# multishift.net
KiCad netlist of a schematic drawn in EAGLE
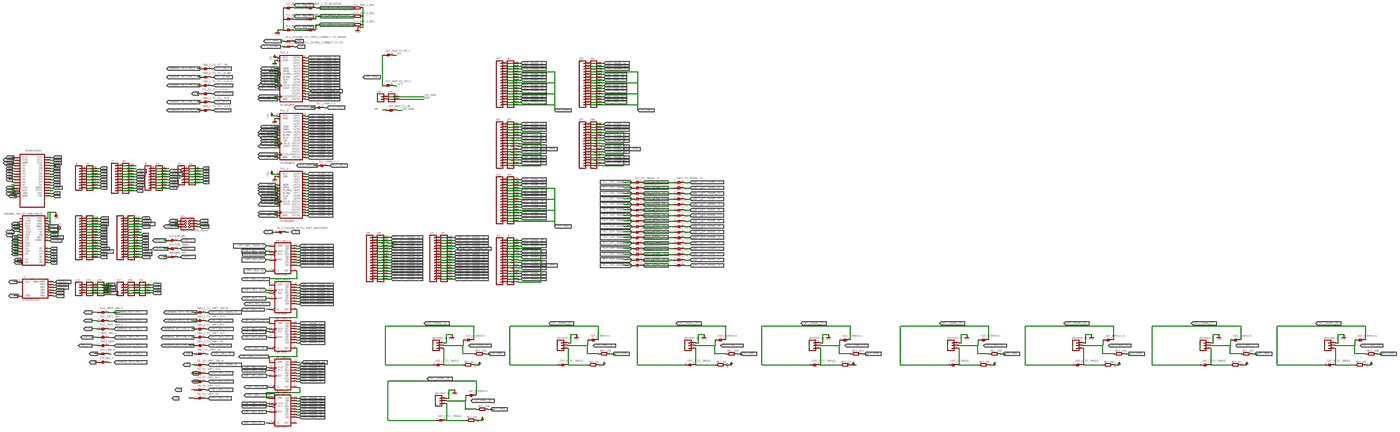
[diagram p0: schematic, sheet 1, overview]
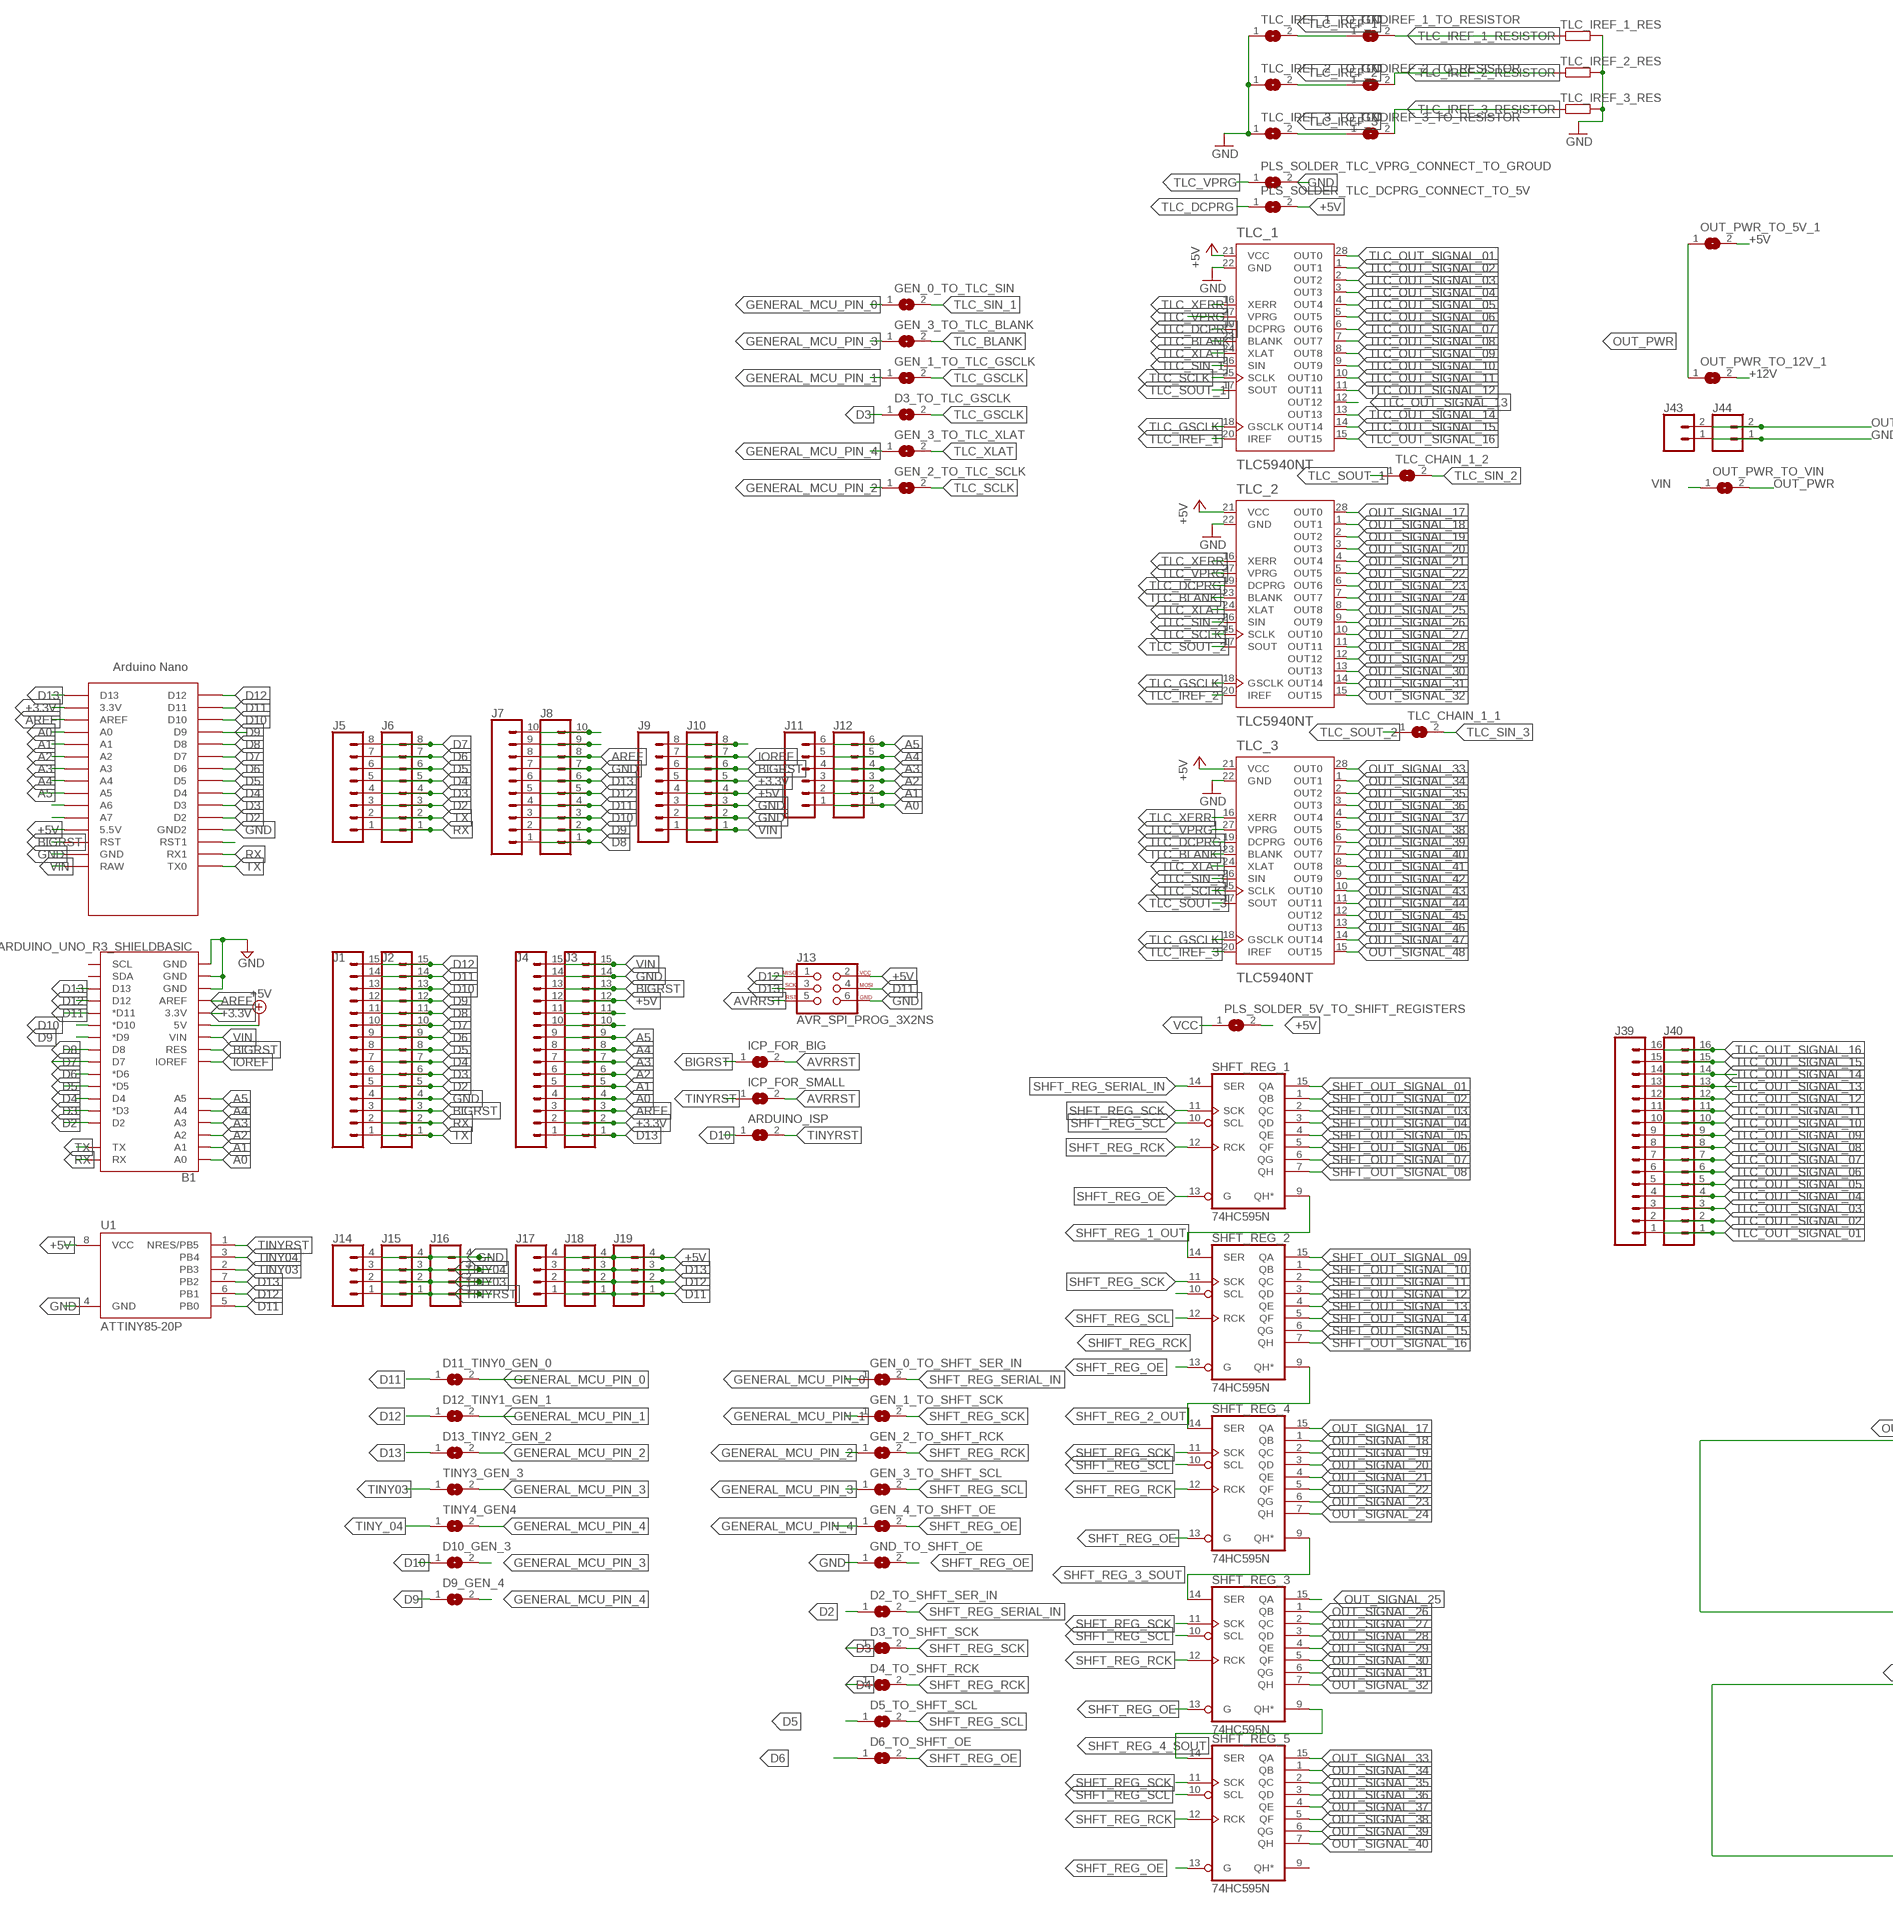
[diagram p1: schematic, sheet 1, part 1 of 4]
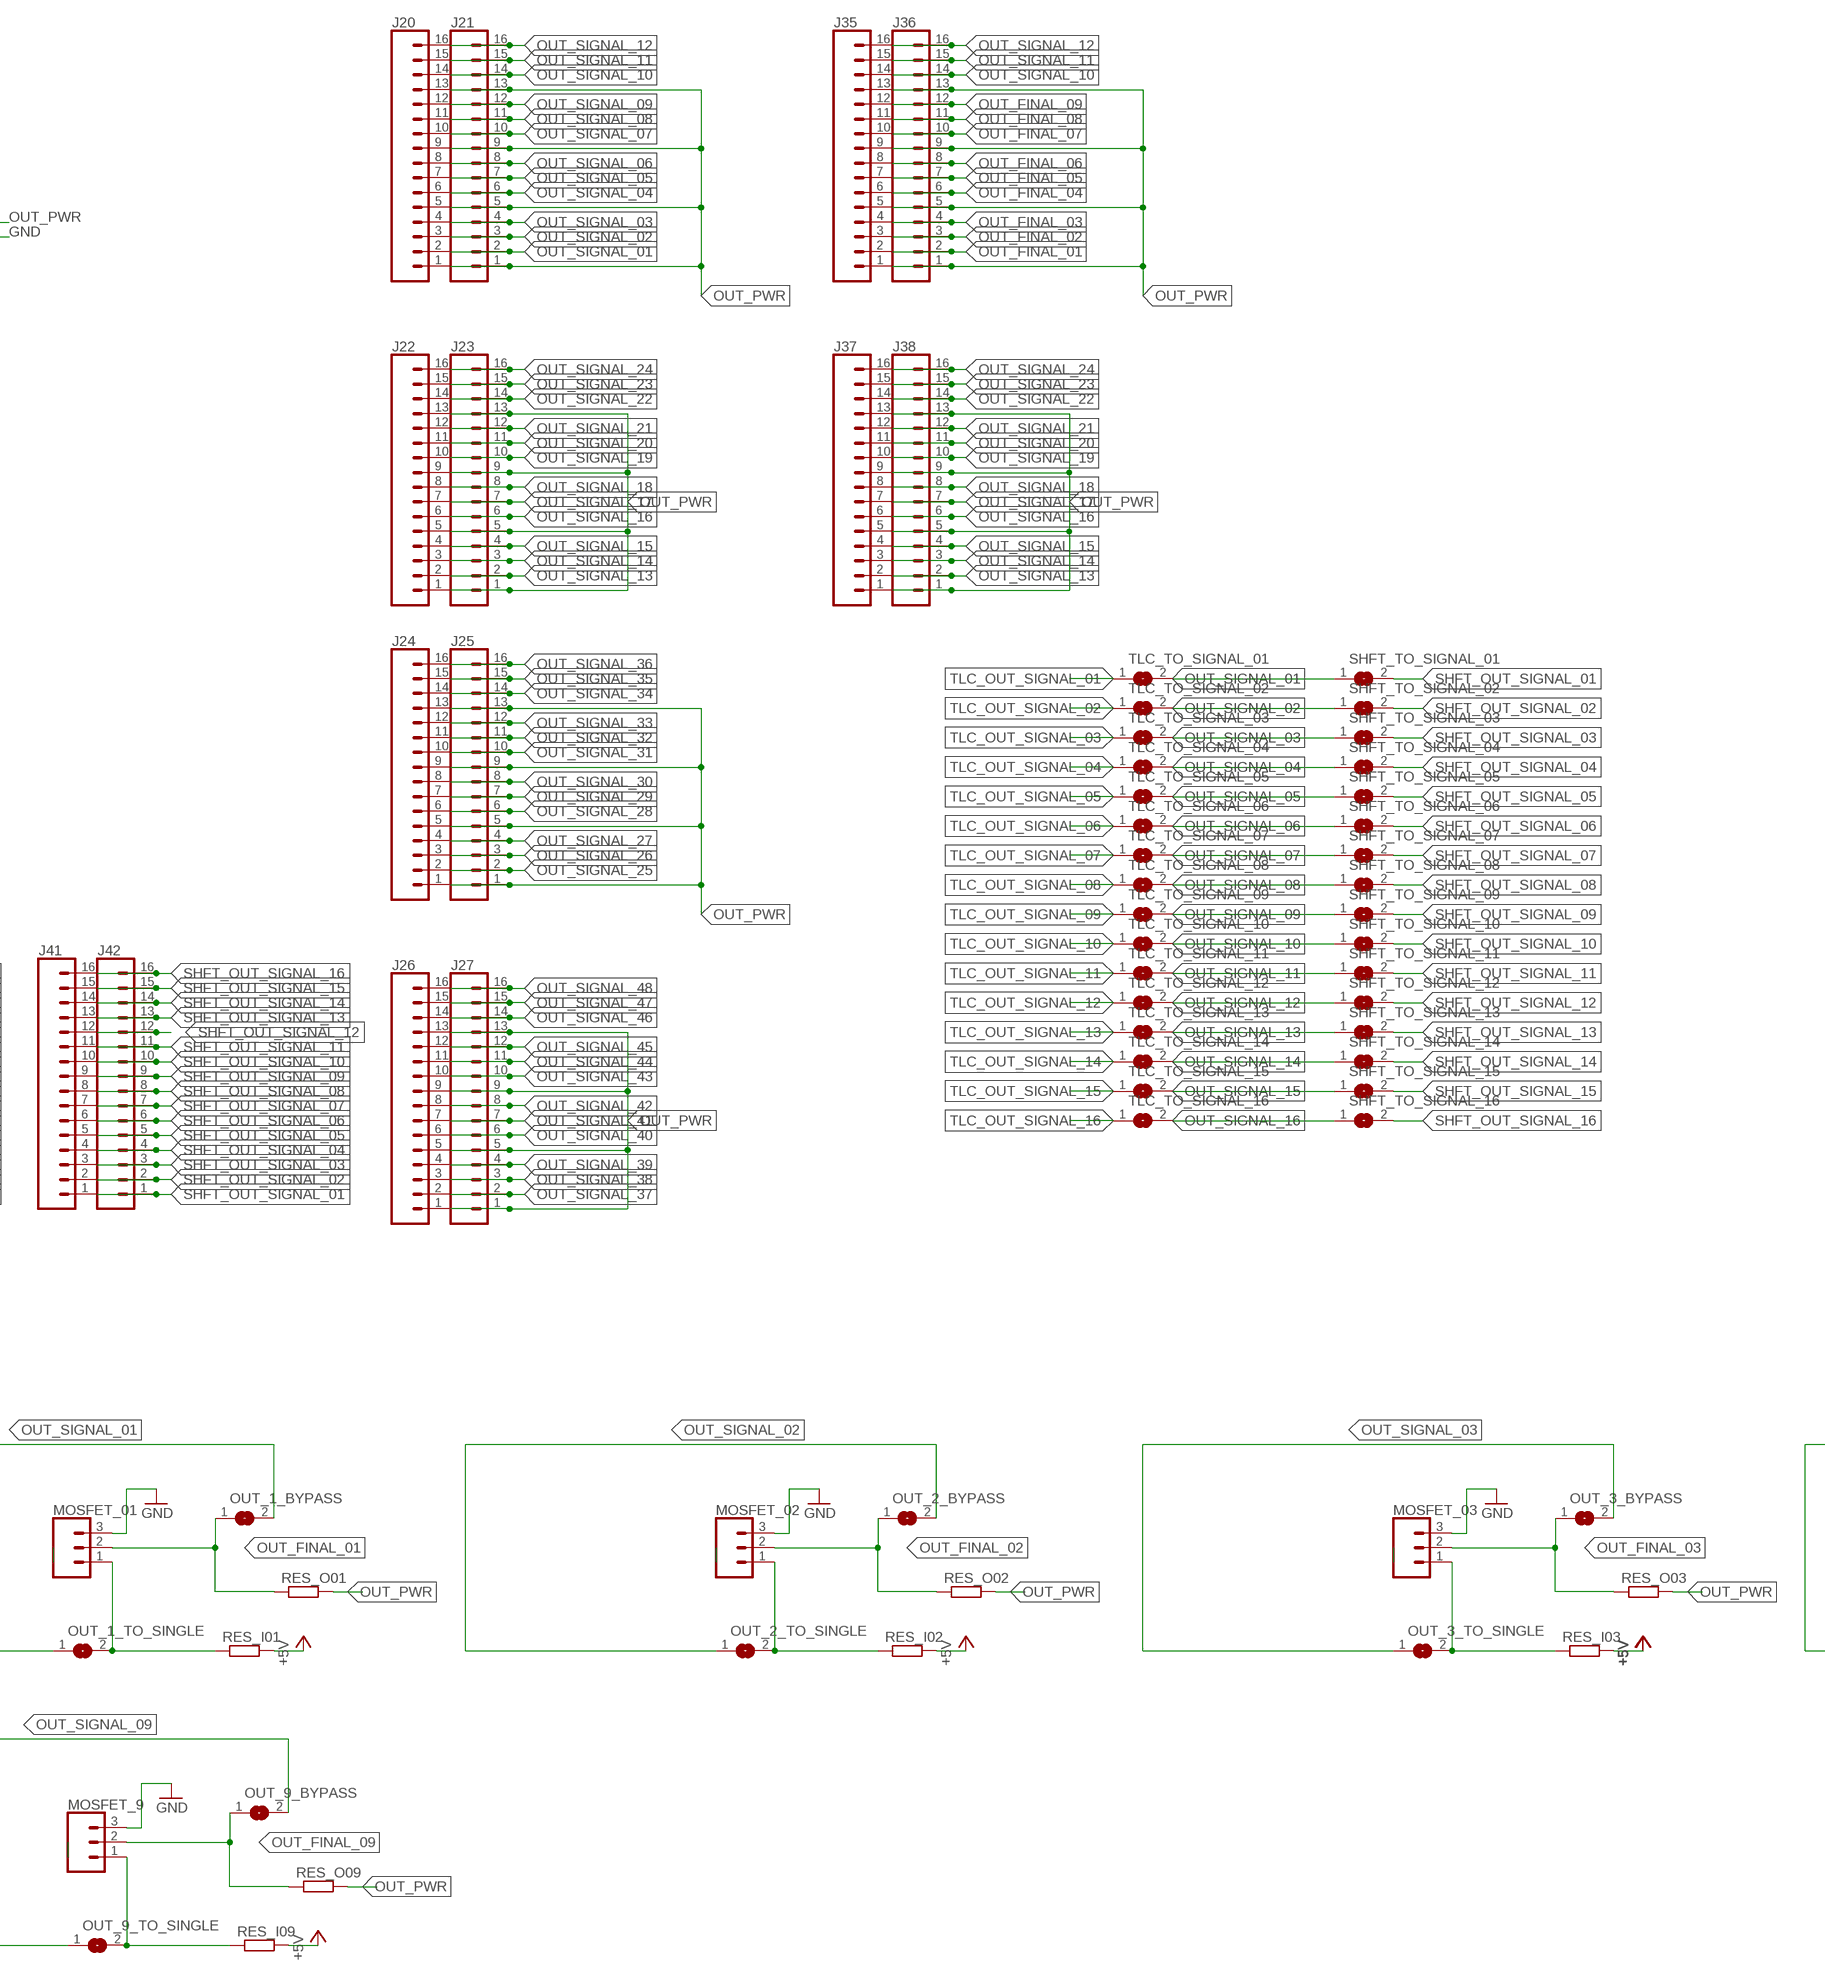
[diagram p2: schematic, sheet 1, part 2 of 4]
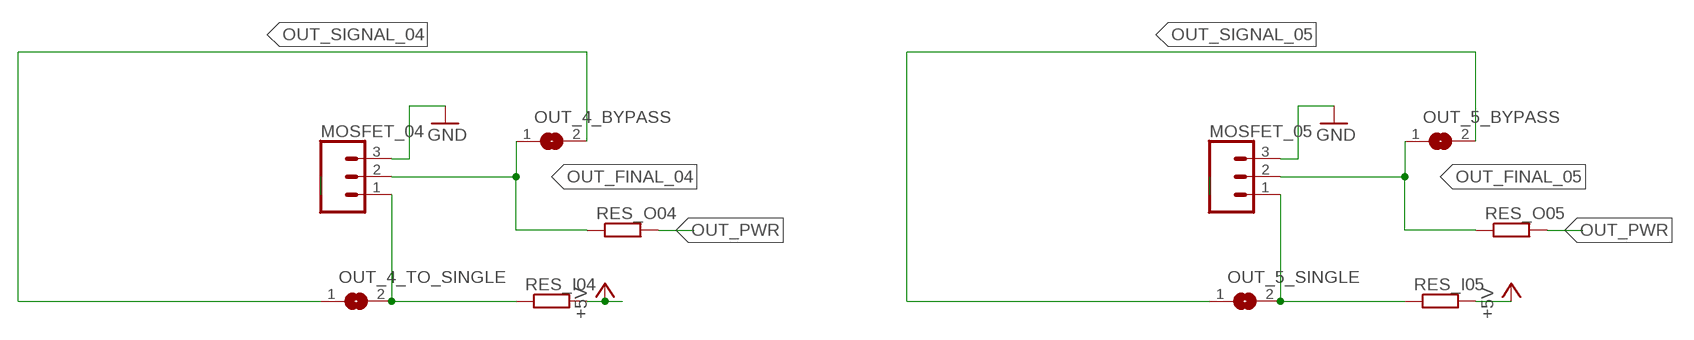
[diagram p3: schematic, sheet 1, part 3 of 4]
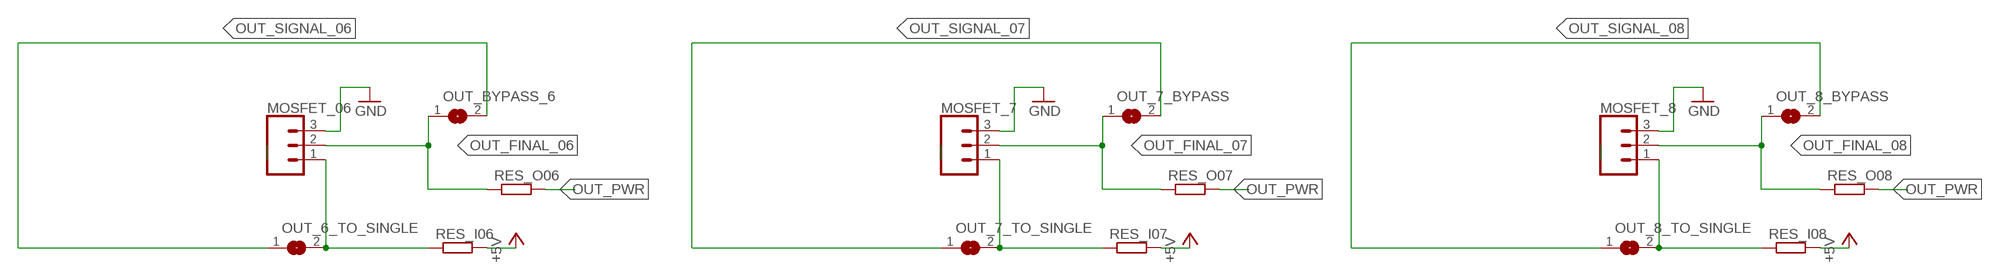
[diagram p4: schematic, sheet 1, part 4 of 4]

(export (version "E")
  (design (tool "Eeschema 10.0.6"))
  (components
    (comp (ref "ARDUINO_ISP")
      (value "SJ")
      (footprint "eagle-import:SJ")
      (libsource (lib "eagle-import") (part "SJ"))
    )
    (comp (ref "B1")
      (value "ARDUINO_UNO_R3_SHIELDBASIC")
      (footprint "eagle-import:UNO_R3_SHIELD")
      (libsource (lib "eagle-import") (part "ARDUINO_UNO_R3_SHIELDBASIC"))
    )
    (comp (ref "D2_TO_SHFT_SER_IN")
      (value "SJ")
      (footprint "eagle-import:SJ")
      (libsource (lib "eagle-import") (part "SJ"))
    )
    (comp (ref "D3_TO_SHFT_SCK")
      (value "SJ")
      (footprint "eagle-import:SJ")
      (libsource (lib "eagle-import") (part "SJ"))
    )
    (comp (ref "D3_TO_TLC_GSCLK")
      (value "SJ")
      (footprint "eagle-import:SJ")
      (libsource (lib "eagle-import") (part "SJ"))
    )
    (comp (ref "D4_TO_SHFT_RCK")
      (value "SJ")
      (footprint "eagle-import:SJ")
      (libsource (lib "eagle-import") (part "SJ"))
    )
    (comp (ref "D5_TO_SHFT_SCL")
      (value "SJ")
      (footprint "eagle-import:SJ")
      (libsource (lib "eagle-import") (part "SJ"))
    )
    (comp (ref "D6_TO_SHFT_OE")
      (value "SJ")
      (footprint "eagle-import:SJ")
      (libsource (lib "eagle-import") (part "SJ"))
    )
    (comp (ref "D9_GEN_4")
      (value "SJ")
      (footprint "eagle-import:SJ")
      (libsource (lib "eagle-import") (part "SJ"))
    )
    (comp (ref "D10_GEN_3")
      (value "SJ")
      (footprint "eagle-import:SJ")
      (libsource (lib "eagle-import") (part "SJ"))
    )
    (comp (ref "D11_TINY0_GEN_0")
      (value "SJ")
      (footprint "eagle-import:SJ")
      (libsource (lib "eagle-import") (part "SJ"))
    )
    (comp (ref "D12_TINY1_GEN_1")
      (value "SJ")
      (footprint "eagle-import:SJ")
      (libsource (lib "eagle-import") (part "SJ"))
    )
    (comp (ref "D13_TINY2_GEN_2")
      (value "SJ")
      (footprint "eagle-import:SJ")
      (libsource (lib "eagle-import") (part "SJ"))
    )
    (comp (ref "GEN_0_TO_SHFT_SER_IN")
      (value "SJ")
      (footprint "eagle-import:SJ")
      (libsource (lib "eagle-import") (part "SJ"))
    )
    (comp (ref "GEN_0_TO_TLC_SIN")
      (value "SJ")
      (footprint "eagle-import:SJ")
      (libsource (lib "eagle-import") (part "SJ"))
    )
    (comp (ref "GEN_1_TO_SHFT_SCK")
      (value "SJ")
      (footprint "eagle-import:SJ")
      (libsource (lib "eagle-import") (part "SJ"))
    )
    (comp (ref "GEN_1_TO_TLC_GSCLK")
      (value "SJ")
      (footprint "eagle-import:SJ")
      (libsource (lib "eagle-import") (part "SJ"))
    )
    (comp (ref "GEN_2_TO_SHFT_RCK")
      (value "SJ")
      (footprint "eagle-import:SJ")
      (libsource (lib "eagle-import") (part "SJ"))
    )
    (comp (ref "GEN_2_TO_TLC_SCLK")
      (value "SJ")
      (footprint "eagle-import:SJ")
      (libsource (lib "eagle-import") (part "SJ"))
    )
    (comp (ref "GEN_3_TO_SHFT_SCL")
      (value "SJ")
      (footprint "eagle-import:SJ")
      (libsource (lib "eagle-import") (part "SJ"))
    )
    (comp (ref "GEN_3_TO_TLC_BLANK")
      (value "SJ")
      (footprint "eagle-import:SJ")
      (libsource (lib "eagle-import") (part "SJ"))
    )
    (comp (ref "GEN_3_TO_TLC_XLAT")
      (value "SJ")
      (footprint "eagle-import:SJ")
      (libsource (lib "eagle-import") (part "SJ"))
    )
    (comp (ref "GEN_4_TO_SHFT_OE")
      (value "SJ")
      (footprint "eagle-import:SJ")
      (libsource (lib "eagle-import") (part "SJ"))
    )
    (comp (ref "GND_TO_SHFT_OE")
      (value "SJ")
      (footprint "eagle-import:SJ")
      (libsource (lib "eagle-import") (part "SJ"))
    )
    (comp (ref "ICP_FOR_BIG")
      (value "SJ")
      (footprint "eagle-import:SJ")
      (libsource (lib "eagle-import") (part "SJ"))
    )
    (comp (ref "ICP_FOR_SMALL")
      (value "SJ")
      (footprint "eagle-import:SJ")
      (libsource (lib "eagle-import") (part "SJ"))
    )
    (comp (ref "J1")
      (value "CONN_15")
      (footprint "eagle-import:1X15")
      (libsource (lib "eagle-import") (part "CONN_15"))
    )
    (comp (ref "J2")
      (value "CONN_15")
      (footprint "eagle-import:1X15")
      (libsource (lib "eagle-import") (part "CONN_15"))
    )
    (comp (ref "J3")
      (value "CONN_15")
      (footprint "eagle-import:1X15")
      (libsource (lib "eagle-import") (part "CONN_15"))
    )
    (comp (ref "J4")
      (value "CONN_15")
      (footprint "eagle-import:1X15")
      (libsource (lib "eagle-import") (part "CONN_15"))
    )
    (comp (ref "J5")
      (value "CONN_08\"")
      (footprint "eagle-import:1X08")
      (libsource (lib "eagle-import") (part "CONN_08{dblquote}"))
    )
    (comp (ref "J6")
      (value "CONN_08\"")
      (footprint "eagle-import:1X08")
      (libsource (lib "eagle-import") (part "CONN_08{dblquote}"))
    )
    (comp (ref "J7")
      (value "CONN_10\"")
      (footprint "eagle-import:1X10")
      (libsource (lib "eagle-import") (part "CONN_10{dblquote}"))
    )
    (comp (ref "J8")
      (value "CONN_10\"")
      (footprint "eagle-import:1X10")
      (libsource (lib "eagle-import") (part "CONN_10{dblquote}"))
    )
    (comp (ref "J9")
      (value "CONN_08\"")
      (footprint "eagle-import:1X08")
      (libsource (lib "eagle-import") (part "CONN_08{dblquote}"))
    )
    (comp (ref "J10")
      (value "CONN_08\"")
      (footprint "eagle-import:1X08")
      (libsource (lib "eagle-import") (part "CONN_08{dblquote}"))
    )
    (comp (ref "J11")
      (value "CONN_06SILK_FEMALE_PTH")
      (footprint "eagle-import:1X06")
      (libsource (lib "eagle-import") (part "CONN_06SILK_FEMALE_PTH"))
    )
    (comp (ref "J12")
      (value "CONN_06SILK_FEMALE_PTH")
      (footprint "eagle-import:1X06")
      (libsource (lib "eagle-import") (part "CONN_06SILK_FEMALE_PTH"))
    )
    (comp (ref "J13")
      (value "AVR_SPI_PROG_3X2NS")
      (footprint "eagle-import:2X3-NS")
      (libsource (lib "eagle-import") (part "AVR_SPI_PROG_3X2NS"))
    )
    (comp (ref "J14")
      (value "CONN_04")
      (footprint "eagle-import:1X04")
      (libsource (lib "eagle-import") (part "CONN_04"))
    )
    (comp (ref "J15")
      (value "CONN_04")
      (footprint "eagle-import:1X04")
      (libsource (lib "eagle-import") (part "CONN_04"))
    )
    (comp (ref "J16")
      (value "CONN_04")
      (footprint "eagle-import:1X04")
      (libsource (lib "eagle-import") (part "CONN_04"))
    )
    (comp (ref "J17")
      (value "CONN_04")
      (footprint "eagle-import:1X04")
      (libsource (lib "eagle-import") (part "CONN_04"))
    )
    (comp (ref "J18")
      (value "CONN_04")
      (footprint "eagle-import:1X04")
      (libsource (lib "eagle-import") (part "CONN_04"))
    )
    (comp (ref "J19")
      (value "CONN_04")
      (footprint "eagle-import:1X04")
      (libsource (lib "eagle-import") (part "CONN_04"))
    )
    (comp (ref "J20")
      (value "CONN_16")
      (footprint "eagle-import:1X16")
      (libsource (lib "eagle-import") (part "CONN_16"))
    )
    (comp (ref "J21")
      (value "CONN_16")
      (footprint "eagle-import:1X16")
      (libsource (lib "eagle-import") (part "CONN_16"))
    )
    (comp (ref "J22")
      (value "CONN_16")
      (footprint "eagle-import:1X16")
      (libsource (lib "eagle-import") (part "CONN_16"))
    )
    (comp (ref "J23")
      (value "CONN_16")
      (footprint "eagle-import:1X16")
      (libsource (lib "eagle-import") (part "CONN_16"))
    )
    (comp (ref "J24")
      (value "CONN_16")
      (footprint "eagle-import:1X16")
      (libsource (lib "eagle-import") (part "CONN_16"))
    )
    (comp (ref "J25")
      (value "CONN_16")
      (footprint "eagle-import:1X16")
      (libsource (lib "eagle-import") (part "CONN_16"))
    )
    (comp (ref "J26")
      (value "CONN_16")
      (footprint "eagle-import:1X16")
      (libsource (lib "eagle-import") (part "CONN_16"))
    )
    (comp (ref "J27")
      (value "CONN_16")
      (footprint "eagle-import:1X16")
      (libsource (lib "eagle-import") (part "CONN_16"))
    )
    (comp (ref "J35")
      (value "CONN_16")
      (footprint "eagle-import:1X16")
      (libsource (lib "eagle-import") (part "CONN_16"))
    )
    (comp (ref "J36")
      (value "CONN_16")
      (footprint "eagle-import:1X16")
      (libsource (lib "eagle-import") (part "CONN_16"))
    )
    (comp (ref "J37")
      (value "CONN_16")
      (footprint "eagle-import:1X16")
      (libsource (lib "eagle-import") (part "CONN_16"))
    )
    (comp (ref "J38")
      (value "CONN_16")
      (footprint "eagle-import:1X16")
      (libsource (lib "eagle-import") (part "CONN_16"))
    )
    (comp (ref "J39")
      (value "CONN_16")
      (footprint "eagle-import:1X16")
      (libsource (lib "eagle-import") (part "CONN_16"))
    )
    (comp (ref "J40")
      (value "CONN_16")
      (footprint "eagle-import:1X16")
      (libsource (lib "eagle-import") (part "CONN_16"))
    )
    (comp (ref "J41")
      (value "CONN_16")
      (footprint "eagle-import:1X16")
      (libsource (lib "eagle-import") (part "CONN_16"))
    )
    (comp (ref "J42")
      (value "CONN_16")
      (footprint "eagle-import:1X16")
      (libsource (lib "eagle-import") (part "CONN_16"))
    )
    (comp (ref "J43")
      (value "CONN_025MM")
      (footprint "eagle-import:SCREWTERMINAL-5MM-2")
      (libsource (lib "eagle-import") (part "CONN_025MM"))
    )
    (comp (ref "J44")
      (value "CONN_025MM")
      (footprint "eagle-import:SCREWTERMINAL-5MM-2")
      (libsource (lib "eagle-import") (part "CONN_025MM"))
    )
    (comp (ref "MOSFET_01")
      (value "CONN_03")
      (footprint "eagle-import:1X03")
      (libsource (lib "eagle-import") (part "CONN_03"))
    )
    (comp (ref "MOSFET_02")
      (value "CONN_03")
      (footprint "eagle-import:1X03")
      (libsource (lib "eagle-import") (part "CONN_03"))
    )
    (comp (ref "MOSFET_03")
      (value "CONN_03")
      (footprint "eagle-import:1X03")
      (libsource (lib "eagle-import") (part "CONN_03"))
    )
    (comp (ref "MOSFET_04")
      (value "CONN_03")
      (footprint "eagle-import:1X03")
      (libsource (lib "eagle-import") (part "CONN_03"))
    )
    (comp (ref "MOSFET_05")
      (value "CONN_03")
      (footprint "eagle-import:1X03")
      (libsource (lib "eagle-import") (part "CONN_03"))
    )
    (comp (ref "MOSFET_06")
      (value "CONN_03")
      (footprint "eagle-import:1X03")
      (libsource (lib "eagle-import") (part "CONN_03"))
    )
    (comp (ref "MOSFET_7")
      (value "CONN_03")
      (footprint "eagle-import:1X03")
      (libsource (lib "eagle-import") (part "CONN_03"))
    )
    (comp (ref "MOSFET_8")
      (value "CONN_03")
      (footprint "eagle-import:1X03")
      (libsource (lib "eagle-import") (part "CONN_03"))
    )
    (comp (ref "MOSFET_9")
      (value "CONN_03")
      (footprint "eagle-import:1X03")
      (libsource (lib "eagle-import") (part "CONN_03"))
    )
    (comp (ref "OUT_1_BYPASS")
      (value "SJ")
      (footprint "eagle-import:SJ")
      (libsource (lib "eagle-import") (part "SJ"))
    )
    (comp (ref "OUT_1_TO_SINGLE")
      (value "SJ")
      (footprint "eagle-import:SJ")
      (libsource (lib "eagle-import") (part "SJ"))
    )
    (comp (ref "OUT_2_BYPASS")
      (value "SJ")
      (footprint "eagle-import:SJ")
      (libsource (lib "eagle-import") (part "SJ"))
    )
    (comp (ref "OUT_2_TO_SINGLE")
      (value "SJ")
      (footprint "eagle-import:SJ")
      (libsource (lib "eagle-import") (part "SJ"))
    )
    (comp (ref "OUT_3_BYPASS")
      (value "SJ")
      (footprint "eagle-import:SJ")
      (libsource (lib "eagle-import") (part "SJ"))
    )
    (comp (ref "OUT_3_TO_SINGLE")
      (value "SJ")
      (footprint "eagle-import:SJ")
      (libsource (lib "eagle-import") (part "SJ"))
    )
    (comp (ref "OUT_4_BYPASS")
      (value "SJ")
      (footprint "eagle-import:SJ")
      (libsource (lib "eagle-import") (part "SJ"))
    )
    (comp (ref "OUT_4_TO_SINGLE")
      (value "SJ")
      (footprint "eagle-import:SJ")
      (libsource (lib "eagle-import") (part "SJ"))
    )
    (comp (ref "OUT_5_BYPASS")
      (value "SJ")
      (footprint "eagle-import:SJ")
      (libsource (lib "eagle-import") (part "SJ"))
    )
    (comp (ref "OUT_5_SINGLE")
      (value "SJ")
      (footprint "eagle-import:SJ")
      (libsource (lib "eagle-import") (part "SJ"))
    )
    (comp (ref "OUT_6_TO_SINGLE")
      (value "SJ")
      (footprint "eagle-import:SJ")
      (libsource (lib "eagle-import") (part "SJ"))
    )
    (comp (ref "OUT_7_BYPASS")
      (value "SJ")
      (footprint "eagle-import:SJ")
      (libsource (lib "eagle-import") (part "SJ"))
    )
    (comp (ref "OUT_7_TO_SINGLE")
      (value "SJ")
      (footprint "eagle-import:SJ")
      (libsource (lib "eagle-import") (part "SJ"))
    )
    (comp (ref "OUT_8_BYPASS")
      (value "SJ")
      (footprint "eagle-import:SJ")
      (libsource (lib "eagle-import") (part "SJ"))
    )
    (comp (ref "OUT_8_TO_SINGLE")
      (value "SJ")
      (footprint "eagle-import:SJ")
      (libsource (lib "eagle-import") (part "SJ"))
    )
    (comp (ref "OUT_9_BYPASS")
      (value "SJ")
      (footprint "eagle-import:SJ")
      (libsource (lib "eagle-import") (part "SJ"))
    )
    (comp (ref "OUT_9_TO_SINGLE")
      (value "SJ")
      (footprint "eagle-import:SJ")
      (libsource (lib "eagle-import") (part "SJ"))
    )
    (comp (ref "OUT_BYPASS_6")
      (value "SJ")
      (footprint "eagle-import:SJ")
      (libsource (lib "eagle-import") (part "SJ"))
    )
    (comp (ref "OUT_PWR_TO_5V_1")
      (value "SJ")
      (footprint "eagle-import:SJ")
      (libsource (lib "eagle-import") (part "SJ"))
    )
    (comp (ref "OUT_PWR_TO_12V_1")
      (value "SJ")
      (footprint "eagle-import:SJ")
      (libsource (lib "eagle-import") (part "SJ"))
    )
    (comp (ref "OUT_PWR_TO_VIN")
      (value "SJ")
      (footprint "eagle-import:SJ")
      (libsource (lib "eagle-import") (part "SJ"))
    )
    (comp (ref "PLS_SOLDER_5V_TO_SHIFT_REGISTERS")
      (value "SJ")
      (footprint "eagle-import:SJ")
      (libsource (lib "eagle-import") (part "SJ"))
    )
    (comp (ref "PLS_SOLDER_TLC_DCPRG_CONNECT_TO_5V")
      (value "SJ")
      (footprint "eagle-import:SJ")
      (libsource (lib "eagle-import") (part "SJ"))
    )
    (comp (ref "PLS_SOLDER_TLC_VPRG_CONNECT_TO_GROUD")
      (value "SJ")
      (footprint "eagle-import:SJ")
      (libsource (lib "eagle-import") (part "SJ"))
    )
    (comp (ref "RES_I01")
      (value "R-EU_0204/7")
      (footprint "eagle-import:0204_7")
      (libsource (lib "eagle-import") (part "R-EU_0204/7"))
    )
    (comp (ref "RES_I02")
      (value "R-EU_0204/7")
      (footprint "eagle-import:0204_7")
      (libsource (lib "eagle-import") (part "R-EU_0204/7"))
    )
    (comp (ref "RES_I03")
      (value "R-EU_0204/7")
      (footprint "eagle-import:0204_7")
      (libsource (lib "eagle-import") (part "R-EU_0204/7"))
    )
    (comp (ref "RES_I04")
      (value "R-EU_0204/7")
      (footprint "eagle-import:0204_7")
      (libsource (lib "eagle-import") (part "R-EU_0204/7"))
    )
    (comp (ref "RES_I05")
      (value "R-EU_0204/7")
      (footprint "eagle-import:0204_7")
      (libsource (lib "eagle-import") (part "R-EU_0204/7"))
    )
    (comp (ref "RES_I06")
      (value "R-EU_0204/7")
      (footprint "eagle-import:0204_7")
      (libsource (lib "eagle-import") (part "R-EU_0204/7"))
    )
    (comp (ref "RES_I07")
      (value "R-EU_0204/7")
      (footprint "eagle-import:0204_7")
      (libsource (lib "eagle-import") (part "R-EU_0204/7"))
    )
    (comp (ref "RES_I08")
      (value "R-EU_0204/7")
      (footprint "eagle-import:0204_7")
      (libsource (lib "eagle-import") (part "R-EU_0204/7"))
    )
    (comp (ref "RES_I09")
      (value "R-EU_0204/7")
      (footprint "eagle-import:0204_7")
      (libsource (lib "eagle-import") (part "R-EU_0204/7"))
    )
    (comp (ref "RES_O01")
      (value "R-EU_0204/7")
      (footprint "eagle-import:0204_7")
      (libsource (lib "eagle-import") (part "R-EU_0204/7"))
    )
    (comp (ref "RES_O02")
      (value "R-EU_0204/7")
      (footprint "eagle-import:0204_7")
      (libsource (lib "eagle-import") (part "R-EU_0204/7"))
    )
    (comp (ref "RES_O03")
      (value "R-EU_0204/7")
      (footprint "eagle-import:0204_7")
      (libsource (lib "eagle-import") (part "R-EU_0204/7"))
    )
    (comp (ref "RES_O04")
      (value "R-EU_0204/7")
      (footprint "eagle-import:0204_7")
      (libsource (lib "eagle-import") (part "R-EU_0204/7"))
    )
    (comp (ref "RES_O05")
      (value "R-EU_0204/7")
      (footprint "eagle-import:0204_7")
      (libsource (lib "eagle-import") (part "R-EU_0204/7"))
    )
    (comp (ref "RES_O06")
      (value "R-EU_0204/7")
      (footprint "eagle-import:0204_7")
      (libsource (lib "eagle-import") (part "R-EU_0204/7"))
    )
    (comp (ref "RES_O07")
      (value "R-EU_0204/7")
      (footprint "eagle-import:0204_7")
      (libsource (lib "eagle-import") (part "R-EU_0204/7"))
    )
    (comp (ref "RES_O08")
      (value "R-EU_0204/7")
      (footprint "eagle-import:0204_7")
      (libsource (lib "eagle-import") (part "R-EU_0204/7"))
    )
    (comp (ref "RES_O09")
      (value "R-EU_0204/7")
      (footprint "eagle-import:0204_7")
      (libsource (lib "eagle-import") (part "R-EU_0204/7"))
    )
    (comp (ref "SHFT_REG_1")
      (value "74HC595N")
      (footprint "eagle-import:DIL16")
      (libsource (lib "eagle-import") (part "74595NHC"))
    )
    (comp (ref "SHFT_REG_2")
      (value "74HC595N")
      (footprint "eagle-import:DIL16")
      (libsource (lib "eagle-import") (part "74595NHC"))
    )
    (comp (ref "SHFT_REG_3")
      (value "74HC595N")
      (footprint "eagle-import:DIL16")
      (libsource (lib "eagle-import") (part "74595NHC"))
    )
    (comp (ref "SHFT_REG_4")
      (value "74HC595N")
      (footprint "eagle-import:DIL16")
      (libsource (lib "eagle-import") (part "74595NHC"))
    )
    (comp (ref "SHFT_REG_5")
      (value "74HC595N")
      (footprint "eagle-import:DIL16")
      (libsource (lib "eagle-import") (part "74595NHC"))
    )
    (comp (ref "SHFT_TO_SIGNAL_01")
      (value "SJ")
      (footprint "eagle-import:SJ")
      (libsource (lib "eagle-import") (part "SJ"))
    )
    (comp (ref "SHFT_TO_SIGNAL_02")
      (value "SJ")
      (footprint "eagle-import:SJ")
      (libsource (lib "eagle-import") (part "SJ"))
    )
    (comp (ref "SHFT_TO_SIGNAL_03")
      (value "SJ")
      (footprint "eagle-import:SJ")
      (libsource (lib "eagle-import") (part "SJ"))
    )
    (comp (ref "SHFT_TO_SIGNAL_04")
      (value "SJ")
      (footprint "eagle-import:SJ")
      (libsource (lib "eagle-import") (part "SJ"))
    )
    (comp (ref "SHFT_TO_SIGNAL_05")
      (value "SJ")
      (footprint "eagle-import:SJ")
      (libsource (lib "eagle-import") (part "SJ"))
    )
    (comp (ref "SHFT_TO_SIGNAL_06")
      (value "SJ")
      (footprint "eagle-import:SJ")
      (libsource (lib "eagle-import") (part "SJ"))
    )
    (comp (ref "SHFT_TO_SIGNAL_07")
      (value "SJ")
      (footprint "eagle-import:SJ")
      (libsource (lib "eagle-import") (part "SJ"))
    )
    (comp (ref "SHFT_TO_SIGNAL_08")
      (value "SJ")
      (footprint "eagle-import:SJ")
      (libsource (lib "eagle-import") (part "SJ"))
    )
    (comp (ref "SHFT_TO_SIGNAL_09")
      (value "SJ")
      (footprint "eagle-import:SJ")
      (libsource (lib "eagle-import") (part "SJ"))
    )
    (comp (ref "SHFT_TO_SIGNAL_10")
      (value "SJ")
      (footprint "eagle-import:SJ")
      (libsource (lib "eagle-import") (part "SJ"))
    )
    (comp (ref "SHFT_TO_SIGNAL_11")
      (value "SJ")
      (footprint "eagle-import:SJ")
      (libsource (lib "eagle-import") (part "SJ"))
    )
    (comp (ref "SHFT_TO_SIGNAL_12")
      (value "SJ")
      (footprint "eagle-import:SJ")
      (libsource (lib "eagle-import") (part "SJ"))
    )
    (comp (ref "SHFT_TO_SIGNAL_13")
      (value "SJ")
      (footprint "eagle-import:SJ")
      (libsource (lib "eagle-import") (part "SJ"))
    )
    (comp (ref "SHFT_TO_SIGNAL_14")
      (value "SJ")
      (footprint "eagle-import:SJ")
      (libsource (lib "eagle-import") (part "SJ"))
    )
    (comp (ref "SHFT_TO_SIGNAL_15")
      (value "SJ")
      (footprint "eagle-import:SJ")
      (libsource (lib "eagle-import") (part "SJ"))
    )
    (comp (ref "SHFT_TO_SIGNAL_16")
      (value "SJ")
      (footprint "eagle-import:SJ")
      (libsource (lib "eagle-import") (part "SJ"))
    )
    (comp (ref "TINY3_GEN_3")
      (value "SJ")
      (footprint "eagle-import:SJ")
      (libsource (lib "eagle-import") (part "SJ"))
    )
    (comp (ref "TINY4_GEN4")
      (value "SJ")
      (footprint "eagle-import:SJ")
      (libsource (lib "eagle-import") (part "SJ"))
    )
    (comp (ref "TLC_1")
      (value "TLC5940NT")
      (footprint "eagle-import:DIL28-3")
      (libsource (lib "eagle-import") (part "TLC5940NT"))
    )
    (comp (ref "TLC_2")
      (value "TLC5940NT")
      (footprint "eagle-import:DIL28-3")
      (libsource (lib "eagle-import") (part "TLC5940NT"))
    )
    (comp (ref "TLC_3")
      (value "TLC5940NT")
      (footprint "eagle-import:DIL28-3")
      (libsource (lib "eagle-import") (part "TLC5940NT"))
    )
    (comp (ref "TLC_CHAIN_1_1")
      (value "SJ")
      (footprint "eagle-import:SJ")
      (libsource (lib "eagle-import") (part "SJ"))
    )
    (comp (ref "TLC_CHAIN_1_2")
      (value "SJ")
      (footprint "eagle-import:SJ")
      (libsource (lib "eagle-import") (part "SJ"))
    )
    (comp (ref "TLC_IREF_1_RES")
      (value "R-EU_0204/7")
      (footprint "eagle-import:0204_7")
      (libsource (lib "eagle-import") (part "R-EU_0204/7"))
    )
    (comp (ref "TLC_IREF_1_TO_GND")
      (value "SJ")
      (footprint "eagle-import:SJ")
      (libsource (lib "eagle-import") (part "SJ"))
    )
    (comp (ref "TLC_IREF_1_TO_RESISTOR")
      (value "SJ")
      (footprint "eagle-import:SJ")
      (libsource (lib "eagle-import") (part "SJ"))
    )
    (comp (ref "TLC_IREF_2_RES")
      (value "R-EU_0204/7")
      (footprint "eagle-import:0204_7")
      (libsource (lib "eagle-import") (part "R-EU_0204/7"))
    )
    (comp (ref "TLC_IREF_2_TO_GND")
      (value "SJ")
      (footprint "eagle-import:SJ")
      (libsource (lib "eagle-import") (part "SJ"))
    )
    (comp (ref "TLC_IREF_2_TO_RESISTOR")
      (value "SJ")
      (footprint "eagle-import:SJ")
      (libsource (lib "eagle-import") (part "SJ"))
    )
    (comp (ref "TLC_IREF_3_RES")
      (value "R-EU_0204/7")
      (footprint "eagle-import:0204_7")
      (libsource (lib "eagle-import") (part "R-EU_0204/7"))
    )
    (comp (ref "TLC_IREF_3_TO_GND")
      (value "SJ")
      (footprint "eagle-import:SJ")
      (libsource (lib "eagle-import") (part "SJ"))
    )
    (comp (ref "TLC_IREF_3_TO_RESISTOR")
      (value "SJ")
      (footprint "eagle-import:SJ")
      (libsource (lib "eagle-import") (part "SJ"))
    )
    (comp (ref "TLC_TO_SIGNAL_01")
      (value "SJ")
      (footprint "eagle-import:SJ")
      (libsource (lib "eagle-import") (part "SJ"))
    )
    (comp (ref "TLC_TO_SIGNAL_02")
      (value "SJ")
      (footprint "eagle-import:SJ")
      (libsource (lib "eagle-import") (part "SJ"))
    )
    (comp (ref "TLC_TO_SIGNAL_03")
      (value "SJ")
      (footprint "eagle-import:SJ")
      (libsource (lib "eagle-import") (part "SJ"))
    )
    (comp (ref "TLC_TO_SIGNAL_04")
      (value "SJ")
      (footprint "eagle-import:SJ")
      (libsource (lib "eagle-import") (part "SJ"))
    )
    (comp (ref "TLC_TO_SIGNAL_05")
      (value "SJ")
      (footprint "eagle-import:SJ")
      (libsource (lib "eagle-import") (part "SJ"))
    )
    (comp (ref "TLC_TO_SIGNAL_06")
      (value "SJ")
      (footprint "eagle-import:SJ")
      (libsource (lib "eagle-import") (part "SJ"))
    )
    (comp (ref "TLC_TO_SIGNAL_07")
      (value "SJ")
      (footprint "eagle-import:SJ")
      (libsource (lib "eagle-import") (part "SJ"))
    )
    (comp (ref "TLC_TO_SIGNAL_08")
      (value "SJ")
      (footprint "eagle-import:SJ")
      (libsource (lib "eagle-import") (part "SJ"))
    )
    (comp (ref "TLC_TO_SIGNAL_09")
      (value "SJ")
      (footprint "eagle-import:SJ")
      (libsource (lib "eagle-import") (part "SJ"))
    )
    (comp (ref "TLC_TO_SIGNAL_10")
      (value "SJ")
      (footprint "eagle-import:SJ")
      (libsource (lib "eagle-import") (part "SJ"))
    )
    (comp (ref "TLC_TO_SIGNAL_11")
      (value "SJ")
      (footprint "eagle-import:SJ")
      (libsource (lib "eagle-import") (part "SJ"))
    )
    (comp (ref "TLC_TO_SIGNAL_12")
      (value "SJ")
      (footprint "eagle-import:SJ")
      (libsource (lib "eagle-import") (part "SJ"))
    )
    (comp (ref "TLC_TO_SIGNAL_13")
      (value "SJ")
      (footprint "eagle-import:SJ")
      (libsource (lib "eagle-import") (part "SJ"))
    )
    (comp (ref "TLC_TO_SIGNAL_14")
      (value "SJ")
      (footprint "eagle-import:SJ")
      (libsource (lib "eagle-import") (part "SJ"))
    )
    (comp (ref "TLC_TO_SIGNAL_15")
      (value "SJ")
      (footprint "eagle-import:SJ")
      (libsource (lib "eagle-import") (part "SJ"))
    )
    (comp (ref "TLC_TO_SIGNAL_16")
      (value "SJ")
      (footprint "eagle-import:SJ")
      (libsource (lib "eagle-import") (part "SJ"))
    )
    (comp (ref "U$1")
      (value "NANO")
      (footprint "eagle-import:NANO")
      (libsource (lib "eagle-import") (part "NANO"))
    )
    (comp (ref "U1")
      (value "ATTINY85-20P")
      (footprint "eagle-import:PDIP08_300MIL")
      (libsource (lib "eagle-import") (part "ATTINY85P-20"))
    )
  )
  (nets
    (net (code "1") (name "+3.3V") (class "Default")
      (node (ref "B1") (pin "3.3V") (pinfunction "3.3V_3.3V") (pintype "bidirectional"))
      (node (ref "J10") (pin "5") (pinfunction "5_5") (pintype "passive"))
      (node (ref "J3") (pin "2") (pinfunction "2_2") (pintype "passive"))
      (node (ref "J4") (pin "2") (pinfunction "2_2") (pintype "passive"))
      (node (ref "J9") (pin "5") (pinfunction "5_5") (pintype "passive"))
      (node (ref "U$1") (pin "3.3V") (pinfunction "3.3V_3.3V") (pintype "bidirectional"))
    )
    (net (code "2") (name "+5V") (class "Default")
      (node (ref "B1") (pin "5V") (pinfunction "5V_5V") (pintype "bidirectional"))
      (node (ref "J10") (pin "4") (pinfunction "4_4") (pintype "passive"))
      (node (ref "J13") (pin "2") (pinfunction "2_2") (pintype "passive"))
      (node (ref "J17") (pin "4") (pinfunction "4_4") (pintype "passive"))
      (node (ref "J18") (pin "4") (pinfunction "4_4") (pintype "passive"))
      (node (ref "J19") (pin "4") (pinfunction "4_4") (pintype "passive"))
      (node (ref "J3") (pin "12") (pinfunction "12_12") (pintype "passive"))
      (node (ref "J4") (pin "12") (pinfunction "12_12") (pintype "passive"))
      (node (ref "J9") (pin "4") (pinfunction "4_4") (pintype "passive"))
      (node (ref "OUT_PWR_TO_5V_1") (pin "2") (pinfunction "2_2") (pintype "passive"))
      (node (ref "PLS_SOLDER_5V_TO_SHIFT_REGISTERS") (pin "2") (pinfunction "2_2") (pintype "passive"))
      (node (ref "PLS_SOLDER_TLC_DCPRG_CONNECT_TO_5V") (pin "2") (pinfunction "2_2") (pintype "passive"))
      (node (ref "RES_I01") (pin "2") (pinfunction "2_2") (pintype "passive"))
      (node (ref "RES_I02") (pin "2") (pinfunction "2_2") (pintype "passive"))
      (node (ref "RES_I03") (pin "2") (pinfunction "2_2") (pintype "passive"))
      (node (ref "RES_I04") (pin "2") (pinfunction "2_2") (pintype "passive"))
      (node (ref "RES_I05") (pin "2") (pinfunction "2_2") (pintype "passive"))
      (node (ref "RES_I06") (pin "2") (pinfunction "2_2") (pintype "passive"))
      (node (ref "RES_I07") (pin "2") (pinfunction "2_2") (pintype "passive"))
      (node (ref "RES_I08") (pin "2") (pinfunction "2_2") (pintype "passive"))
      (node (ref "RES_I09") (pin "2") (pinfunction "2_2") (pintype "passive"))
      (node (ref "TLC_1") (pin "21") (pinfunction "VCC_21") (pintype "power_in"))
      (node (ref "TLC_2") (pin "21") (pinfunction "VCC_21") (pintype "power_in"))
      (node (ref "TLC_3") (pin "21") (pinfunction "VCC_21") (pintype "power_in"))
      (node (ref "U$1") (pin "5V") (pinfunction "5.5V_5V") (pintype "bidirectional"))
      (node (ref "U1") (pin "8") (pinfunction "VCC_8") (pintype "power_in"))
    )
    (net (code "3") (name "/+12V") (class "Default")
      (node (ref "OUT_PWR_TO_12V_1") (pin "2") (pinfunction "2_2") (pintype "passive"))
    )
    (net (code "4") (name "A0") (class "Default")
      (node (ref "B1") (pin "A0") (pinfunction "A0_A0") (pintype "bidirectional"))
      (node (ref "J11") (pin "1") (pinfunction "1_1") (pintype "passive"))
      (node (ref "J12") (pin "1") (pinfunction "1_1") (pintype "passive"))
      (node (ref "J3") (pin "4") (pinfunction "4_4") (pintype "passive"))
      (node (ref "J4") (pin "4") (pinfunction "4_4") (pintype "passive"))
      (node (ref "U$1") (pin "A0") (pinfunction "A0_A0") (pintype "bidirectional"))
    )
    (net (code "5") (name "A1") (class "Default")
      (node (ref "B1") (pin "A1") (pinfunction "A1_A1") (pintype "bidirectional"))
      (node (ref "J11") (pin "2") (pinfunction "2_2") (pintype "passive"))
      (node (ref "J12") (pin "2") (pinfunction "2_2") (pintype "passive"))
      (node (ref "J3") (pin "5") (pinfunction "5_5") (pintype "passive"))
      (node (ref "J4") (pin "5") (pinfunction "5_5") (pintype "passive"))
      (node (ref "U$1") (pin "A1") (pinfunction "A1_A1") (pintype "bidirectional"))
    )
    (net (code "6") (name "A2") (class "Default")
      (node (ref "B1") (pin "A2") (pinfunction "A2_A2") (pintype "bidirectional"))
      (node (ref "J11") (pin "3") (pinfunction "3_3") (pintype "passive"))
      (node (ref "J12") (pin "3") (pinfunction "3_3") (pintype "passive"))
      (node (ref "J3") (pin "6") (pinfunction "6_6") (pintype "passive"))
      (node (ref "J4") (pin "6") (pinfunction "6_6") (pintype "passive"))
      (node (ref "U$1") (pin "A2") (pinfunction "A2_A2") (pintype "bidirectional"))
    )
    (net (code "7") (name "A3") (class "Default")
      (node (ref "B1") (pin "A3") (pinfunction "A3_A3") (pintype "bidirectional"))
      (node (ref "J11") (pin "4") (pinfunction "4_4") (pintype "passive"))
      (node (ref "J12") (pin "4") (pinfunction "4_4") (pintype "passive"))
      (node (ref "J3") (pin "7") (pinfunction "7_7") (pintype "passive"))
      (node (ref "J4") (pin "7") (pinfunction "7_7") (pintype "passive"))
      (node (ref "U$1") (pin "A3") (pinfunction "A3_A3") (pintype "bidirectional"))
    )
    (net (code "8") (name "A4") (class "Default")
      (node (ref "B1") (pin "A4") (pinfunction "A4_A4") (pintype "bidirectional"))
      (node (ref "J11") (pin "5") (pinfunction "5_5") (pintype "passive"))
      (node (ref "J12") (pin "5") (pinfunction "5_5") (pintype "passive"))
      (node (ref "J3") (pin "8") (pinfunction "8_8") (pintype "passive"))
      (node (ref "J4") (pin "8") (pinfunction "8_8") (pintype "passive"))
      (node (ref "U$1") (pin "A4") (pinfunction "A4_A4") (pintype "bidirectional"))
    )
    (net (code "9") (name "A5") (class "Default")
      (node (ref "B1") (pin "A5") (pinfunction "A5_A5") (pintype "bidirectional"))
      (node (ref "J11") (pin "6") (pinfunction "6_6") (pintype "passive"))
      (node (ref "J12") (pin "6") (pinfunction "6_6") (pintype "passive"))
      (node (ref "J3") (pin "9") (pinfunction "9_9") (pintype "passive"))
      (node (ref "J4") (pin "9") (pinfunction "9_9") (pintype "passive"))
      (node (ref "U$1") (pin "A5") (pinfunction "A5_A5") (pintype "bidirectional"))
    )
    (net (code "10") (name "AREF") (class "Default")
      (node (ref "B1") (pin "AREF") (pinfunction "AREF_AREF") (pintype "bidirectional"))
      (node (ref "J3") (pin "3") (pinfunction "3_3") (pintype "passive"))
      (node (ref "J4") (pin "3") (pinfunction "3_3") (pintype "passive"))
      (node (ref "J7") (pin "8") (pinfunction "8_8") (pintype "passive"))
      (node (ref "J8") (pin "8") (pinfunction "8_8") (pintype "passive"))
      (node (ref "U$1") (pin "AREF") (pinfunction "AREF_AREF") (pintype "bidirectional"))
    )
    (net (code "11") (name "AVRRST") (class "Default")
      (node (ref "ICP_FOR_BIG") (pin "2") (pinfunction "2_2") (pintype "passive"))
      (node (ref "ICP_FOR_SMALL") (pin "2") (pinfunction "2_2") (pintype "passive"))
      (node (ref "J13") (pin "5") (pinfunction "5_5") (pintype "passive"))
    )
    (net (code "12") (name "BIGRST") (class "Default")
      (node (ref "B1") (pin "RES") (pinfunction "RES_RES") (pintype "bidirectional"))
      (node (ref "ICP_FOR_BIG") (pin "1") (pinfunction "1_1") (pintype "passive"))
      (node (ref "J1") (pin "3") (pinfunction "3_3") (pintype "passive"))
      (node (ref "J10") (pin "6") (pinfunction "6_6") (pintype "passive"))
      (node (ref "J2") (pin "3") (pinfunction "3_3") (pintype "passive"))
      (node (ref "J3") (pin "13") (pinfunction "13_13") (pintype "passive"))
      (node (ref "J4") (pin "13") (pinfunction "13_13") (pintype "passive"))
      (node (ref "J9") (pin "6") (pinfunction "6_6") (pintype "passive"))
      (node (ref "U$1") (pin "RST") (pinfunction "RST_RST") (pintype "bidirectional"))
    )
    (net (code "13") (name "D2") (class "Default")
      (node (ref "B1") (pin "D2") (pinfunction "D2_D2") (pintype "bidirectional"))
      (node (ref "D2_TO_SHFT_SER_IN") (pin "1") (pinfunction "1_1") (pintype "passive"))
      (node (ref "J1") (pin "5") (pinfunction "5_5") (pintype "passive"))
      (node (ref "J2") (pin "5") (pinfunction "5_5") (pintype "passive"))
      (node (ref "J5") (pin "3") (pinfunction "3_3") (pintype "passive"))
      (node (ref "J6") (pin "3") (pinfunction "3_3") (pintype "passive"))
      (node (ref "U$1") (pin "D2") (pinfunction "D2_D2") (pintype "bidirectional"))
    )
    (net (code "14") (name "D3") (class "Default")
      (node (ref "B1") (pin "D3") (pinfunction "*D3_D3") (pintype "bidirectional"))
      (node (ref "D3_TO_SHFT_SCK") (pin "1") (pinfunction "1_1") (pintype "passive"))
      (node (ref "D3_TO_TLC_GSCLK") (pin "1") (pinfunction "1_1") (pintype "passive"))
      (node (ref "J1") (pin "6") (pinfunction "6_6") (pintype "passive"))
      (node (ref "J2") (pin "6") (pinfunction "6_6") (pintype "passive"))
      (node (ref "J5") (pin "4") (pinfunction "4_4") (pintype "passive"))
      (node (ref "J6") (pin "4") (pinfunction "4_4") (pintype "passive"))
      (node (ref "U$1") (pin "D3") (pinfunction "D3_D3") (pintype "bidirectional"))
    )
    (net (code "15") (name "D4") (class "Default")
      (node (ref "B1") (pin "D4") (pinfunction "D4_D4") (pintype "bidirectional"))
      (node (ref "D4_TO_SHFT_RCK") (pin "1") (pinfunction "1_1") (pintype "passive"))
      (node (ref "J1") (pin "7") (pinfunction "7_7") (pintype "passive"))
      (node (ref "J2") (pin "7") (pinfunction "7_7") (pintype "passive"))
      (node (ref "J5") (pin "5") (pinfunction "5_5") (pintype "passive"))
      (node (ref "J6") (pin "5") (pinfunction "5_5") (pintype "passive"))
      (node (ref "U$1") (pin "D4") (pinfunction "D4_D4") (pintype "bidirectional"))
    )
    (net (code "16") (name "D5") (class "Default")
      (node (ref "B1") (pin "D5") (pinfunction "*D5_D5") (pintype "bidirectional"))
      (node (ref "D5_TO_SHFT_SCL") (pin "1") (pinfunction "1_1") (pintype "passive"))
      (node (ref "J1") (pin "8") (pinfunction "8_8") (pintype "passive"))
      (node (ref "J2") (pin "8") (pinfunction "8_8") (pintype "passive"))
      (node (ref "J5") (pin "6") (pinfunction "6_6") (pintype "passive"))
      (node (ref "J6") (pin "6") (pinfunction "6_6") (pintype "passive"))
      (node (ref "U$1") (pin "D5") (pinfunction "D5_D5") (pintype "bidirectional"))
    )
    (net (code "17") (name "D6") (class "Default")
      (node (ref "B1") (pin "D6") (pinfunction "*D6_D6") (pintype "bidirectional"))
      (node (ref "D6_TO_SHFT_OE") (pin "1") (pinfunction "1_1") (pintype "passive"))
      (node (ref "J1") (pin "9") (pinfunction "9_9") (pintype "passive"))
      (node (ref "J2") (pin "9") (pinfunction "9_9") (pintype "passive"))
      (node (ref "J5") (pin "7") (pinfunction "7_7") (pintype "passive"))
      (node (ref "J6") (pin "7") (pinfunction "7_7") (pintype "passive"))
      (node (ref "U$1") (pin "D6") (pinfunction "D6_D6") (pintype "bidirectional"))
    )
    (net (code "18") (name "D7") (class "Default")
      (node (ref "B1") (pin "D7") (pinfunction "D7_D7") (pintype "bidirectional"))
      (node (ref "J1") (pin "10") (pinfunction "10_10") (pintype "passive"))
      (node (ref "J2") (pin "10") (pinfunction "10_10") (pintype "passive"))
      (node (ref "J5") (pin "8") (pinfunction "8_8") (pintype "passive"))
      (node (ref "J6") (pin "8") (pinfunction "8_8") (pintype "passive"))
      (node (ref "U$1") (pin "D7") (pinfunction "D7_D7") (pintype "bidirectional"))
    )
    (net (code "19") (name "D8") (class "Default")
      (node (ref "B1") (pin "D8") (pinfunction "D8_D8") (pintype "bidirectional"))
      (node (ref "J1") (pin "11") (pinfunction "11_11") (pintype "passive"))
      (node (ref "J2") (pin "11") (pinfunction "11_11") (pintype "passive"))
      (node (ref "J7") (pin "1") (pinfunction "1_1") (pintype "passive"))
      (node (ref "J8") (pin "1") (pinfunction "1_1") (pintype "passive"))
      (node (ref "U$1") (pin "D8") (pinfunction "D8_D8") (pintype "bidirectional"))
    )
    (net (code "20") (name "D9") (class "Default")
      (node (ref "B1") (pin "D9") (pinfunction "*D9_D9") (pintype "bidirectional"))
      (node (ref "D9_GEN_4") (pin "1") (pinfunction "1_1") (pintype "passive"))
      (node (ref "J1") (pin "12") (pinfunction "12_12") (pintype "passive"))
      (node (ref "J2") (pin "12") (pinfunction "12_12") (pintype "passive"))
      (node (ref "J7") (pin "2") (pinfunction "2_2") (pintype "passive"))
      (node (ref "J8") (pin "2") (pinfunction "2_2") (pintype "passive"))
      (node (ref "U$1") (pin "D9") (pinfunction "D9_D9") (pintype "bidirectional"))
    )
    (net (code "21") (name "D10") (class "Default")
      (node (ref "ARDUINO_ISP") (pin "1") (pinfunction "1_1") (pintype "passive"))
      (node (ref "B1") (pin "D10") (pinfunction "*D10_D10") (pintype "bidirectional"))
      (node (ref "D10_GEN_3") (pin "1") (pinfunction "1_1") (pintype "passive"))
      (node (ref "J1") (pin "13") (pinfunction "13_13") (pintype "passive"))
      (node (ref "J2") (pin "13") (pinfunction "13_13") (pintype "passive"))
      (node (ref "J7") (pin "3") (pinfunction "3_3") (pintype "passive"))
      (node (ref "J8") (pin "3") (pinfunction "3_3") (pintype "passive"))
      (node (ref "U$1") (pin "D10") (pinfunction "D10_D10") (pintype "bidirectional"))
    )
    (net (code "22") (name "D11") (class "Default")
      (node (ref "B1") (pin "D11") (pinfunction "*D11_D11") (pintype "bidirectional"))
      (node (ref "D11_TINY0_GEN_0") (pin "1") (pinfunction "1_1") (pintype "passive"))
      (node (ref "J1") (pin "14") (pinfunction "14_14") (pintype "passive"))
      (node (ref "J13") (pin "4") (pinfunction "4_4") (pintype "passive"))
      (node (ref "J17") (pin "1") (pinfunction "1_1") (pintype "passive"))
      (node (ref "J18") (pin "1") (pinfunction "1_1") (pintype "passive"))
      (node (ref "J19") (pin "1") (pinfunction "1_1") (pintype "passive"))
      (node (ref "J2") (pin "14") (pinfunction "14_14") (pintype "passive"))
      (node (ref "J7") (pin "4") (pinfunction "4_4") (pintype "passive"))
      (node (ref "J8") (pin "4") (pinfunction "4_4") (pintype "passive"))
      (node (ref "U$1") (pin "D11") (pinfunction "D11_D11") (pintype "bidirectional"))
      (node (ref "U1") (pin "5") (pinfunction "PB0_5") (pintype "bidirectional"))
    )
    (net (code "23") (name "D12") (class "Default")
      (node (ref "B1") (pin "D12") (pinfunction "D12_D12") (pintype "bidirectional"))
      (node (ref "D12_TINY1_GEN_1") (pin "1") (pinfunction "1_1") (pintype "passive"))
      (node (ref "J1") (pin "15") (pinfunction "15_15") (pintype "passive"))
      (node (ref "J13") (pin "1") (pinfunction "1_1") (pintype "passive"))
      (node (ref "J17") (pin "2") (pinfunction "2_2") (pintype "passive"))
      (node (ref "J18") (pin "2") (pinfunction "2_2") (pintype "passive"))
      (node (ref "J19") (pin "2") (pinfunction "2_2") (pintype "passive"))
      (node (ref "J2") (pin "15") (pinfunction "15_15") (pintype "passive"))
      (node (ref "J7") (pin "5") (pinfunction "5_5") (pintype "passive"))
      (node (ref "J8") (pin "5") (pinfunction "5_5") (pintype "passive"))
      (node (ref "U$1") (pin "D12") (pinfunction "D12_D12") (pintype "bidirectional"))
      (node (ref "U1") (pin "6") (pinfunction "PB1_6") (pintype "bidirectional"))
    )
    (net (code "24") (name "D13") (class "Default")
      (node (ref "B1") (pin "D13") (pinfunction "D13_D13") (pintype "bidirectional"))
      (node (ref "D13_TINY2_GEN_2") (pin "1") (pinfunction "1_1") (pintype "passive"))
      (node (ref "J13") (pin "3") (pinfunction "3_3") (pintype "passive"))
      (node (ref "J17") (pin "3") (pinfunction "3_3") (pintype "passive"))
      (node (ref "J18") (pin "3") (pinfunction "3_3") (pintype "passive"))
      (node (ref "J19") (pin "3") (pinfunction "3_3") (pintype "passive"))
      (node (ref "J3") (pin "1") (pinfunction "1_1") (pintype "passive"))
      (node (ref "J4") (pin "1") (pinfunction "1_1") (pintype "passive"))
      (node (ref "J7") (pin "6") (pinfunction "6_6") (pintype "passive"))
      (node (ref "J8") (pin "6") (pinfunction "6_6") (pintype "passive"))
      (node (ref "U$1") (pin "D13") (pinfunction "D13_D13") (pintype "bidirectional"))
      (node (ref "U1") (pin "7") (pinfunction "PB2_7") (pintype "bidirectional"))
    )
    (net (code "25") (name "GENERAL_MCU_PIN_0") (class "Default")
      (node (ref "D11_TINY0_GEN_0") (pin "2") (pinfunction "2_2") (pintype "passive"))
      (node (ref "GEN_0_TO_SHFT_SER_IN") (pin "1") (pinfunction "1_1") (pintype "passive"))
      (node (ref "GEN_0_TO_TLC_SIN") (pin "1") (pinfunction "1_1") (pintype "passive"))
    )
    (net (code "26") (name "GENERAL_MCU_PIN_1") (class "Default")
      (node (ref "D12_TINY1_GEN_1") (pin "2") (pinfunction "2_2") (pintype "passive"))
      (node (ref "GEN_1_TO_SHFT_SCK") (pin "1") (pinfunction "1_1") (pintype "passive"))
      (node (ref "GEN_1_TO_TLC_GSCLK") (pin "1") (pinfunction "1_1") (pintype "passive"))
    )
    (net (code "27") (name "GENERAL_MCU_PIN_2") (class "Default")
      (node (ref "D13_TINY2_GEN_2") (pin "2") (pinfunction "2_2") (pintype "passive"))
      (node (ref "GEN_2_TO_SHFT_RCK") (pin "1") (pinfunction "1_1") (pintype "passive"))
      (node (ref "GEN_2_TO_TLC_SCLK") (pin "1") (pinfunction "1_1") (pintype "passive"))
    )
    (net (code "28") (name "GENERAL_MCU_PIN_3") (class "Default")
      (node (ref "D10_GEN_3") (pin "2") (pinfunction "2_2") (pintype "passive"))
      (node (ref "GEN_3_TO_SHFT_SCL") (pin "1") (pinfunction "1_1") (pintype "passive"))
      (node (ref "GEN_3_TO_TLC_BLANK") (pin "1") (pinfunction "1_1") (pintype "passive"))
      (node (ref "TINY3_GEN_3") (pin "2") (pinfunction "2_2") (pintype "passive"))
    )
    (net (code "29") (name "GENERAL_MCU_PIN_4") (class "Default")
      (node (ref "D9_GEN_4") (pin "2") (pinfunction "2_2") (pintype "passive"))
      (node (ref "GEN_3_TO_TLC_XLAT") (pin "1") (pinfunction "1_1") (pintype "passive"))
      (node (ref "GEN_4_TO_SHFT_OE") (pin "1") (pinfunction "1_1") (pintype "passive"))
      (node (ref "TINY4_GEN4") (pin "2") (pinfunction "2_2") (pintype "passive"))
    )
    (net (code "30") (name "GND") (class "Default")
      (node (ref "B1") (pin "GND@0") (pinfunction "GND_GND@0") (pintype "bidirectional"))
      (node (ref "B1") (pin "GND@1") (pinfunction "GND_GND@1") (pintype "bidirectional"))
      (node (ref "B1") (pin "GND@2") (pinfunction "GND_GND@2") (pintype "bidirectional"))
      (node (ref "GND_TO_SHFT_OE") (pin "1") (pinfunction "1_1") (pintype "passive"))
      (node (ref "J1") (pin "4") (pinfunction "4_4") (pintype "passive"))
      (node (ref "J10") (pin "2") (pinfunction "2_2") (pintype "passive"))
      (node (ref "J10") (pin "3") (pinfunction "3_3") (pintype "passive"))
      (node (ref "J13") (pin "6") (pinfunction "6_6") (pintype "passive"))
      (node (ref "J14") (pin "4") (pinfunction "4_4") (pintype "passive"))
      (node (ref "J15") (pin "4") (pinfunction "4_4") (pintype "passive"))
      (node (ref "J16") (pin "4") (pinfunction "4_4") (pintype "passive"))
      (node (ref "J2") (pin "4") (pinfunction "4_4") (pintype "passive"))
      (node (ref "J3") (pin "14") (pinfunction "14_14") (pintype "passive"))
      (node (ref "J4") (pin "14") (pinfunction "14_14") (pintype "passive"))
      (node (ref "J43") (pin "1") (pinfunction "1_1") (pintype "passive"))
      (node (ref "J44") (pin "1") (pinfunction "1_1") (pintype "passive"))
      (node (ref "J7") (pin "7") (pinfunction "7_7") (pintype "passive"))
      (node (ref "J8") (pin "7") (pinfunction "7_7") (pintype "passive"))
      (node (ref "J9") (pin "2") (pinfunction "2_2") (pintype "passive"))
      (node (ref "J9") (pin "3") (pinfunction "3_3") (pintype "passive"))
      (node (ref "MOSFET_01") (pin "3") (pinfunction "3_3") (pintype "passive"))
      (node (ref "MOSFET_02") (pin "3") (pinfunction "3_3") (pintype "passive"))
      (node (ref "MOSFET_03") (pin "3") (pinfunction "3_3") (pintype "passive"))
      (node (ref "MOSFET_04") (pin "3") (pinfunction "3_3") (pintype "passive"))
      (node (ref "MOSFET_05") (pin "3") (pinfunction "3_3") (pintype "passive"))
      (node (ref "MOSFET_06") (pin "3") (pinfunction "3_3") (pintype "passive"))
      (node (ref "MOSFET_7") (pin "3") (pinfunction "3_3") (pintype "passive"))
      (node (ref "MOSFET_8") (pin "3") (pinfunction "3_3") (pintype "passive"))
      (node (ref "MOSFET_9") (pin "3") (pinfunction "3_3") (pintype "passive"))
      (node (ref "PLS_SOLDER_TLC_VPRG_CONNECT_TO_GROUD") (pin "2") (pinfunction "2_2") (pintype "passive"))
      (node (ref "TLC_1") (pin "22") (pinfunction "GND_22") (pintype "power_in"))
      (node (ref "TLC_2") (pin "22") (pinfunction "GND_22") (pintype "power_in"))
      (node (ref "TLC_3") (pin "22") (pinfunction "GND_22") (pintype "power_in"))
      (node (ref "TLC_IREF_1_RES") (pin "2") (pinfunction "2_2") (pintype "passive"))
      (node (ref "TLC_IREF_1_TO_GND") (pin "1") (pinfunction "1_1") (pintype "passive"))
      (node (ref "TLC_IREF_2_RES") (pin "2") (pinfunction "2_2") (pintype "passive"))
      (node (ref "TLC_IREF_2_TO_GND") (pin "1") (pinfunction "1_1") (pintype "passive"))
      (node (ref "TLC_IREF_3_RES") (pin "2") (pinfunction "2_2") (pintype "passive"))
      (node (ref "TLC_IREF_3_TO_GND") (pin "1") (pinfunction "1_1") (pintype "passive"))
      (node (ref "U$1") (pin "GND") (pinfunction "GND_GND") (pintype "bidirectional"))
      (node (ref "U$1") (pin "GND1") (pinfunction "GND2_GND1") (pintype "bidirectional"))
      (node (ref "U1") (pin "4") (pinfunction "GND_4") (pintype "power_in"))
    )
    (net (code "31") (name "IOREF") (class "Default")
      (node (ref "B1") (pin "IOREF") (pinfunction "IOREF_IOREF") (pintype "bidirectional"))
      (node (ref "J10") (pin "7") (pinfunction "7_7") (pintype "passive"))
      (node (ref "J9") (pin "7") (pinfunction "7_7") (pintype "passive"))
    )
    (net (code "32") (name "Net-(J3-Pad10)") (class "Default")
      (node (ref "J3") (pin "10") (pinfunction "10_10") (pintype "passive"))
      (node (ref "J4") (pin "10") (pinfunction "10_10") (pintype "passive"))
    )
    (net (code "33") (name "Net-(J3-Pad11)") (class "Default")
      (node (ref "J3") (pin "11") (pinfunction "11_11") (pintype "passive"))
      (node (ref "J4") (pin "11") (pinfunction "11_11") (pintype "passive"))
    )
    (net (code "34") (name "Net-(J7-Pad9)") (class "Default")
      (node (ref "J7") (pin "9") (pinfunction "9_9") (pintype "passive"))
      (node (ref "J8") (pin "9") (pinfunction "9_9") (pintype "passive"))
    )
    (net (code "35") (name "Net-(J7-Pad10)") (class "Default")
      (node (ref "J7") (pin "10") (pinfunction "10_10") (pintype "passive"))
      (node (ref "J8") (pin "10") (pinfunction "10_10") (pintype "passive"))
    )
    (net (code "36") (name "Net-(J10-Pad8)") (class "Default")
      (node (ref "J10") (pin "8") (pinfunction "8_8") (pintype "passive"))
      (node (ref "J9") (pin "8") (pinfunction "8_8") (pintype "passive"))
    )
    (net (code "37") (name "Net-(MOSFET_01-Pad1)") (class "Default")
      (node (ref "MOSFET_01") (pin "1") (pinfunction "1_1") (pintype "passive"))
      (node (ref "OUT_1_TO_SINGLE") (pin "2") (pinfunction "2_2") (pintype "passive"))
      (node (ref "RES_I01") (pin "1") (pinfunction "1_1") (pintype "passive"))
    )
    (net (code "38") (name "Net-(MOSFET_02-Pad1)") (class "Default")
      (node (ref "MOSFET_02") (pin "1") (pinfunction "1_1") (pintype "passive"))
      (node (ref "OUT_2_TO_SINGLE") (pin "2") (pinfunction "2_2") (pintype "passive"))
      (node (ref "RES_I02") (pin "1") (pinfunction "1_1") (pintype "passive"))
    )
    (net (code "39") (name "Net-(MOSFET_03-Pad1)") (class "Default")
      (node (ref "MOSFET_03") (pin "1") (pinfunction "1_1") (pintype "passive"))
      (node (ref "OUT_3_TO_SINGLE") (pin "2") (pinfunction "2_2") (pintype "passive"))
      (node (ref "RES_I03") (pin "1") (pinfunction "1_1") (pintype "passive"))
    )
    (net (code "40") (name "Net-(MOSFET_04-Pad1)") (class "Default")
      (node (ref "MOSFET_04") (pin "1") (pinfunction "1_1") (pintype "passive"))
      (node (ref "OUT_4_TO_SINGLE") (pin "2") (pinfunction "2_2") (pintype "passive"))
      (node (ref "RES_I04") (pin "1") (pinfunction "1_1") (pintype "passive"))
    )
    (net (code "41") (name "Net-(MOSFET_05-Pad1)") (class "Default")
      (node (ref "MOSFET_05") (pin "1") (pinfunction "1_1") (pintype "passive"))
      (node (ref "OUT_5_SINGLE") (pin "2") (pinfunction "2_2") (pintype "passive"))
      (node (ref "RES_I05") (pin "1") (pinfunction "1_1") (pintype "passive"))
    )
    (net (code "42") (name "Net-(MOSFET_06-Pad1)") (class "Default")
      (node (ref "MOSFET_06") (pin "1") (pinfunction "1_1") (pintype "passive"))
      (node (ref "OUT_6_TO_SINGLE") (pin "2") (pinfunction "2_2") (pintype "passive"))
      (node (ref "RES_I06") (pin "1") (pinfunction "1_1") (pintype "passive"))
    )
    (net (code "43") (name "Net-(MOSFET_7-Pad1)") (class "Default")
      (node (ref "MOSFET_7") (pin "1") (pinfunction "1_1") (pintype "passive"))
      (node (ref "OUT_7_TO_SINGLE") (pin "2") (pinfunction "2_2") (pintype "passive"))
      (node (ref "RES_I07") (pin "1") (pinfunction "1_1") (pintype "passive"))
    )
    (net (code "44") (name "Net-(MOSFET_8-Pad1)") (class "Default")
      (node (ref "MOSFET_8") (pin "1") (pinfunction "1_1") (pintype "passive"))
      (node (ref "OUT_8_TO_SINGLE") (pin "2") (pinfunction "2_2") (pintype "passive"))
      (node (ref "RES_I08") (pin "1") (pinfunction "1_1") (pintype "passive"))
    )
    (net (code "45") (name "Net-(MOSFET_9-Pad1)") (class "Default")
      (node (ref "MOSFET_9") (pin "1") (pinfunction "1_1") (pintype "passive"))
      (node (ref "OUT_9_TO_SINGLE") (pin "2") (pinfunction "2_2") (pintype "passive"))
      (node (ref "RES_I09") (pin "1") (pinfunction "1_1") (pintype "passive"))
    )
    (net (code "46") (name "OUT_FINAL_01") (class "Default")
      (node (ref "J35") (pin "2") (pinfunction "2_2") (pintype "passive"))
      (node (ref "J36") (pin "2") (pinfunction "2_2") (pintype "passive"))
      (node (ref "MOSFET_01") (pin "2") (pinfunction "2_2") (pintype "passive"))
      (node (ref "OUT_1_BYPASS") (pin "1") (pinfunction "1_1") (pintype "passive"))
      (node (ref "RES_O01") (pin "1") (pinfunction "1_1") (pintype "passive"))
    )
    (net (code "47") (name "OUT_FINAL_02") (class "Default")
      (node (ref "J35") (pin "3") (pinfunction "3_3") (pintype "passive"))
      (node (ref "J36") (pin "3") (pinfunction "3_3") (pintype "passive"))
      (node (ref "MOSFET_02") (pin "2") (pinfunction "2_2") (pintype "passive"))
      (node (ref "OUT_2_BYPASS") (pin "1") (pinfunction "1_1") (pintype "passive"))
      (node (ref "RES_O02") (pin "1") (pinfunction "1_1") (pintype "passive"))
    )
    (net (code "48") (name "OUT_FINAL_03") (class "Default")
      (node (ref "J35") (pin "4") (pinfunction "4_4") (pintype "passive"))
      (node (ref "J36") (pin "4") (pinfunction "4_4") (pintype "passive"))
      (node (ref "MOSFET_03") (pin "2") (pinfunction "2_2") (pintype "passive"))
      (node (ref "OUT_3_BYPASS") (pin "1") (pinfunction "1_1") (pintype "passive"))
      (node (ref "RES_O03") (pin "1") (pinfunction "1_1") (pintype "passive"))
    )
    (net (code "49") (name "OUT_FINAL_04") (class "Default")
      (node (ref "J35") (pin "6") (pinfunction "6_6") (pintype "passive"))
      (node (ref "J36") (pin "6") (pinfunction "6_6") (pintype "passive"))
      (node (ref "MOSFET_04") (pin "2") (pinfunction "2_2") (pintype "passive"))
      (node (ref "OUT_4_BYPASS") (pin "1") (pinfunction "1_1") (pintype "passive"))
      (node (ref "RES_O04") (pin "1") (pinfunction "1_1") (pintype "passive"))
    )
    (net (code "50") (name "OUT_FINAL_05") (class "Default")
      (node (ref "J35") (pin "7") (pinfunction "7_7") (pintype "passive"))
      (node (ref "J36") (pin "7") (pinfunction "7_7") (pintype "passive"))
      (node (ref "MOSFET_05") (pin "2") (pinfunction "2_2") (pintype "passive"))
      (node (ref "OUT_5_BYPASS") (pin "1") (pinfunction "1_1") (pintype "passive"))
      (node (ref "RES_O05") (pin "1") (pinfunction "1_1") (pintype "passive"))
    )
    (net (code "51") (name "OUT_FINAL_06") (class "Default")
      (node (ref "J35") (pin "8") (pinfunction "8_8") (pintype "passive"))
      (node (ref "J36") (pin "8") (pinfunction "8_8") (pintype "passive"))
      (node (ref "MOSFET_06") (pin "2") (pinfunction "2_2") (pintype "passive"))
      (node (ref "OUT_BYPASS_6") (pin "1") (pinfunction "1_1") (pintype "passive"))
      (node (ref "RES_O06") (pin "1") (pinfunction "1_1") (pintype "passive"))
    )
    (net (code "52") (name "OUT_FINAL_07") (class "Default")
      (node (ref "J35") (pin "10") (pinfunction "10_10") (pintype "passive"))
      (node (ref "J36") (pin "10") (pinfunction "10_10") (pintype "passive"))
      (node (ref "MOSFET_7") (pin "2") (pinfunction "2_2") (pintype "passive"))
      (node (ref "OUT_7_BYPASS") (pin "1") (pinfunction "1_1") (pintype "passive"))
      (node (ref "RES_O07") (pin "1") (pinfunction "1_1") (pintype "passive"))
    )
    (net (code "53") (name "OUT_FINAL_08") (class "Default")
      (node (ref "J35") (pin "11") (pinfunction "11_11") (pintype "passive"))
      (node (ref "J36") (pin "11") (pinfunction "11_11") (pintype "passive"))
      (node (ref "MOSFET_8") (pin "2") (pinfunction "2_2") (pintype "passive"))
      (node (ref "OUT_8_BYPASS") (pin "1") (pinfunction "1_1") (pintype "passive"))
      (node (ref "RES_O08") (pin "1") (pinfunction "1_1") (pintype "passive"))
    )
    (net (code "54") (name "OUT_FINAL_09") (class "Default")
      (node (ref "J35") (pin "12") (pinfunction "12_12") (pintype "passive"))
      (node (ref "J36") (pin "12") (pinfunction "12_12") (pintype "passive"))
      (node (ref "MOSFET_9") (pin "2") (pinfunction "2_2") (pintype "passive"))
      (node (ref "OUT_9_BYPASS") (pin "1") (pinfunction "1_1") (pintype "passive"))
      (node (ref "RES_O09") (pin "1") (pinfunction "1_1") (pintype "passive"))
    )
    (net (code "55") (name "OUT_PWR") (class "Default")
      (node (ref "J20") (pin "1") (pinfunction "1_1") (pintype "passive"))
      (node (ref "J20") (pin "13") (pinfunction "13_13") (pintype "passive"))
      (node (ref "J20") (pin "5") (pinfunction "5_5") (pintype "passive"))
      (node (ref "J20") (pin "9") (pinfunction "9_9") (pintype "passive"))
      (node (ref "J21") (pin "1") (pinfunction "1_1") (pintype "passive"))
      (node (ref "J21") (pin "13") (pinfunction "13_13") (pintype "passive"))
      (node (ref "J21") (pin "5") (pinfunction "5_5") (pintype "passive"))
      (node (ref "J21") (pin "9") (pinfunction "9_9") (pintype "passive"))
      (node (ref "J22") (pin "1") (pinfunction "1_1") (pintype "passive"))
      (node (ref "J22") (pin "13") (pinfunction "13_13") (pintype "passive"))
      (node (ref "J22") (pin "5") (pinfunction "5_5") (pintype "passive"))
      (node (ref "J22") (pin "9") (pinfunction "9_9") (pintype "passive"))
      (node (ref "J23") (pin "1") (pinfunction "1_1") (pintype "passive"))
      (node (ref "J23") (pin "13") (pinfunction "13_13") (pintype "passive"))
      (node (ref "J23") (pin "5") (pinfunction "5_5") (pintype "passive"))
      (node (ref "J23") (pin "9") (pinfunction "9_9") (pintype "passive"))
      (node (ref "J24") (pin "1") (pinfunction "1_1") (pintype "passive"))
      (node (ref "J24") (pin "13") (pinfunction "13_13") (pintype "passive"))
      (node (ref "J24") (pin "5") (pinfunction "5_5") (pintype "passive"))
      (node (ref "J24") (pin "9") (pinfunction "9_9") (pintype "passive"))
      (node (ref "J25") (pin "1") (pinfunction "1_1") (pintype "passive"))
      (node (ref "J25") (pin "13") (pinfunction "13_13") (pintype "passive"))
      (node (ref "J25") (pin "5") (pinfunction "5_5") (pintype "passive"))
      (node (ref "J25") (pin "9") (pinfunction "9_9") (pintype "passive"))
      (node (ref "J26") (pin "1") (pinfunction "1_1") (pintype "passive"))
      (node (ref "J26") (pin "13") (pinfunction "13_13") (pintype "passive"))
      (node (ref "J26") (pin "5") (pinfunction "5_5") (pintype "passive"))
      (node (ref "J26") (pin "9") (pinfunction "9_9") (pintype "passive"))
      (node (ref "J27") (pin "1") (pinfunction "1_1") (pintype "passive"))
      (node (ref "J27") (pin "13") (pinfunction "13_13") (pintype "passive"))
      (node (ref "J27") (pin "5") (pinfunction "5_5") (pintype "passive"))
      (node (ref "J27") (pin "9") (pinfunction "9_9") (pintype "passive"))
      (node (ref "J35") (pin "1") (pinfunction "1_1") (pintype "passive"))
      (node (ref "J35") (pin "13") (pinfunction "13_13") (pintype "passive"))
      (node (ref "J35") (pin "5") (pinfunction "5_5") (pintype "passive"))
      (node (ref "J35") (pin "9") (pinfunction "9_9") (pintype "passive"))
      (node (ref "J36") (pin "1") (pinfunction "1_1") (pintype "passive"))
      (node (ref "J36") (pin "13") (pinfunction "13_13") (pintype "passive"))
      (node (ref "J36") (pin "5") (pinfunction "5_5") (pintype "passive"))
      (node (ref "J36") (pin "9") (pinfunction "9_9") (pintype "passive"))
      (node (ref "J37") (pin "1") (pinfunction "1_1") (pintype "passive"))
      (node (ref "J37") (pin "13") (pinfunction "13_13") (pintype "passive"))
      (node (ref "J37") (pin "5") (pinfunction "5_5") (pintype "passive"))
      (node (ref "J37") (pin "9") (pinfunction "9_9") (pintype "passive"))
      (node (ref "J38") (pin "1") (pinfunction "1_1") (pintype "passive"))
      (node (ref "J38") (pin "13") (pinfunction "13_13") (pintype "passive"))
      (node (ref "J38") (pin "5") (pinfunction "5_5") (pintype "passive"))
      (node (ref "J38") (pin "9") (pinfunction "9_9") (pintype "passive"))
      (node (ref "J43") (pin "2") (pinfunction "2_2") (pintype "passive"))
      (node (ref "J44") (pin "2") (pinfunction "2_2") (pintype "passive"))
      (node (ref "OUT_PWR_TO_12V_1") (pin "1") (pinfunction "1_1") (pintype "passive"))
      (node (ref "OUT_PWR_TO_5V_1") (pin "1") (pinfunction "1_1") (pintype "passive"))
      (node (ref "OUT_PWR_TO_VIN") (pin "2") (pinfunction "2_2") (pintype "passive"))
      (node (ref "RES_O01") (pin "2") (pinfunction "2_2") (pintype "passive"))
      (node (ref "RES_O02") (pin "2") (pinfunction "2_2") (pintype "passive"))
      (node (ref "RES_O03") (pin "2") (pinfunction "2_2") (pintype "passive"))
      (node (ref "RES_O04") (pin "2") (pinfunction "2_2") (pintype "passive"))
      (node (ref "RES_O05") (pin "2") (pinfunction "2_2") (pintype "passive"))
      (node (ref "RES_O06") (pin "2") (pinfunction "2_2") (pintype "passive"))
      (node (ref "RES_O07") (pin "2") (pinfunction "2_2") (pintype "passive"))
      (node (ref "RES_O08") (pin "2") (pinfunction "2_2") (pintype "passive"))
      (node (ref "RES_O09") (pin "2") (pinfunction "2_2") (pintype "passive"))
    )
    (net (code "56") (name "OUT_SIGNAL_01") (class "Default")
      (node (ref "J20") (pin "2") (pinfunction "2_2") (pintype "passive"))
      (node (ref "J21") (pin "2") (pinfunction "2_2") (pintype "passive"))
      (node (ref "OUT_1_BYPASS") (pin "2") (pinfunction "2_2") (pintype "passive"))
      (node (ref "OUT_1_TO_SINGLE") (pin "1") (pinfunction "1_1") (pintype "passive"))
      (node (ref "SHFT_TO_SIGNAL_01") (pin "1") (pinfunction "1_1") (pintype "passive"))
      (node (ref "TLC_TO_SIGNAL_01") (pin "2") (pinfunction "2_2") (pintype "passive"))
    )
    (net (code "57") (name "OUT_SIGNAL_02") (class "Default")
      (node (ref "J20") (pin "3") (pinfunction "3_3") (pintype "passive"))
      (node (ref "J21") (pin "3") (pinfunction "3_3") (pintype "passive"))
      (node (ref "OUT_2_BYPASS") (pin "2") (pinfunction "2_2") (pintype "passive"))
      (node (ref "OUT_2_TO_SINGLE") (pin "1") (pinfunction "1_1") (pintype "passive"))
      (node (ref "SHFT_TO_SIGNAL_02") (pin "1") (pinfunction "1_1") (pintype "passive"))
      (node (ref "TLC_TO_SIGNAL_02") (pin "2") (pinfunction "2_2") (pintype "passive"))
    )
    (net (code "58") (name "OUT_SIGNAL_03") (class "Default")
      (node (ref "J20") (pin "4") (pinfunction "4_4") (pintype "passive"))
      (node (ref "J21") (pin "4") (pinfunction "4_4") (pintype "passive"))
      (node (ref "OUT_3_BYPASS") (pin "2") (pinfunction "2_2") (pintype "passive"))
      (node (ref "OUT_3_TO_SINGLE") (pin "1") (pinfunction "1_1") (pintype "passive"))
      (node (ref "SHFT_TO_SIGNAL_03") (pin "1") (pinfunction "1_1") (pintype "passive"))
      (node (ref "TLC_TO_SIGNAL_03") (pin "2") (pinfunction "2_2") (pintype "passive"))
    )
    (net (code "59") (name "OUT_SIGNAL_04") (class "Default")
      (node (ref "J20") (pin "6") (pinfunction "6_6") (pintype "passive"))
      (node (ref "J21") (pin "6") (pinfunction "6_6") (pintype "passive"))
      (node (ref "OUT_4_BYPASS") (pin "2") (pinfunction "2_2") (pintype "passive"))
      (node (ref "OUT_4_TO_SINGLE") (pin "1") (pinfunction "1_1") (pintype "passive"))
      (node (ref "SHFT_TO_SIGNAL_04") (pin "1") (pinfunction "1_1") (pintype "passive"))
      (node (ref "TLC_TO_SIGNAL_04") (pin "2") (pinfunction "2_2") (pintype "passive"))
    )
    (net (code "60") (name "OUT_SIGNAL_05") (class "Default")
      (node (ref "J20") (pin "7") (pinfunction "7_7") (pintype "passive"))
      (node (ref "J21") (pin "7") (pinfunction "7_7") (pintype "passive"))
      (node (ref "OUT_5_BYPASS") (pin "2") (pinfunction "2_2") (pintype "passive"))
      (node (ref "OUT_5_SINGLE") (pin "1") (pinfunction "1_1") (pintype "passive"))
      (node (ref "SHFT_TO_SIGNAL_05") (pin "1") (pinfunction "1_1") (pintype "passive"))
      (node (ref "TLC_TO_SIGNAL_05") (pin "2") (pinfunction "2_2") (pintype "passive"))
    )
    (net (code "61") (name "OUT_SIGNAL_06") (class "Default")
      (node (ref "J20") (pin "8") (pinfunction "8_8") (pintype "passive"))
      (node (ref "J21") (pin "8") (pinfunction "8_8") (pintype "passive"))
      (node (ref "OUT_6_TO_SINGLE") (pin "1") (pinfunction "1_1") (pintype "passive"))
      (node (ref "OUT_BYPASS_6") (pin "2") (pinfunction "2_2") (pintype "passive"))
      (node (ref "SHFT_TO_SIGNAL_06") (pin "1") (pinfunction "1_1") (pintype "passive"))
      (node (ref "TLC_TO_SIGNAL_06") (pin "2") (pinfunction "2_2") (pintype "passive"))
    )
    (net (code "62") (name "OUT_SIGNAL_07") (class "Default")
      (node (ref "J20") (pin "10") (pinfunction "10_10") (pintype "passive"))
      (node (ref "J21") (pin "10") (pinfunction "10_10") (pintype "passive"))
      (node (ref "OUT_7_BYPASS") (pin "2") (pinfunction "2_2") (pintype "passive"))
      (node (ref "OUT_7_TO_SINGLE") (pin "1") (pinfunction "1_1") (pintype "passive"))
      (node (ref "SHFT_TO_SIGNAL_07") (pin "1") (pinfunction "1_1") (pintype "passive"))
      (node (ref "TLC_TO_SIGNAL_07") (pin "2") (pinfunction "2_2") (pintype "passive"))
    )
    (net (code "63") (name "OUT_SIGNAL_08") (class "Default")
      (node (ref "J20") (pin "11") (pinfunction "11_11") (pintype "passive"))
      (node (ref "J21") (pin "11") (pinfunction "11_11") (pintype "passive"))
      (node (ref "OUT_8_BYPASS") (pin "2") (pinfunction "2_2") (pintype "passive"))
      (node (ref "OUT_8_TO_SINGLE") (pin "1") (pinfunction "1_1") (pintype "passive"))
      (node (ref "SHFT_TO_SIGNAL_08") (pin "1") (pinfunction "1_1") (pintype "passive"))
      (node (ref "TLC_TO_SIGNAL_08") (pin "2") (pinfunction "2_2") (pintype "passive"))
    )
    (net (code "64") (name "OUT_SIGNAL_09") (class "Default")
      (node (ref "J20") (pin "12") (pinfunction "12_12") (pintype "passive"))
      (node (ref "J21") (pin "12") (pinfunction "12_12") (pintype "passive"))
      (node (ref "OUT_9_BYPASS") (pin "2") (pinfunction "2_2") (pintype "passive"))
      (node (ref "OUT_9_TO_SINGLE") (pin "1") (pinfunction "1_1") (pintype "passive"))
      (node (ref "SHFT_TO_SIGNAL_09") (pin "1") (pinfunction "1_1") (pintype "passive"))
      (node (ref "TLC_TO_SIGNAL_09") (pin "2") (pinfunction "2_2") (pintype "passive"))
    )
    (net (code "65") (name "OUT_SIGNAL_10") (class "Default")
      (node (ref "J20") (pin "14") (pinfunction "14_14") (pintype "passive"))
      (node (ref "J21") (pin "14") (pinfunction "14_14") (pintype "passive"))
      (node (ref "J35") (pin "14") (pinfunction "14_14") (pintype "passive"))
      (node (ref "J36") (pin "14") (pinfunction "14_14") (pintype "passive"))
      (node (ref "SHFT_TO_SIGNAL_10") (pin "1") (pinfunction "1_1") (pintype "passive"))
      (node (ref "TLC_TO_SIGNAL_10") (pin "2") (pinfunction "2_2") (pintype "passive"))
    )
    (net (code "66") (name "OUT_SIGNAL_11") (class "Default")
      (node (ref "J20") (pin "15") (pinfunction "15_15") (pintype "passive"))
      (node (ref "J21") (pin "15") (pinfunction "15_15") (pintype "passive"))
      (node (ref "J35") (pin "15") (pinfunction "15_15") (pintype "passive"))
      (node (ref "J36") (pin "15") (pinfunction "15_15") (pintype "passive"))
      (node (ref "SHFT_TO_SIGNAL_11") (pin "1") (pinfunction "1_1") (pintype "passive"))
      (node (ref "TLC_TO_SIGNAL_11") (pin "2") (pinfunction "2_2") (pintype "passive"))
    )
    (net (code "67") (name "OUT_SIGNAL_12") (class "Default")
      (node (ref "J20") (pin "16") (pinfunction "16_16") (pintype "passive"))
      (node (ref "J21") (pin "16") (pinfunction "16_16") (pintype "passive"))
      (node (ref "J35") (pin "16") (pinfunction "16_16") (pintype "passive"))
      (node (ref "J36") (pin "16") (pinfunction "16_16") (pintype "passive"))
      (node (ref "SHFT_TO_SIGNAL_12") (pin "1") (pinfunction "1_1") (pintype "passive"))
      (node (ref "TLC_TO_SIGNAL_12") (pin "2") (pinfunction "2_2") (pintype "passive"))
    )
    (net (code "68") (name "OUT_SIGNAL_13") (class "Default")
      (node (ref "J22") (pin "2") (pinfunction "2_2") (pintype "passive"))
      (node (ref "J23") (pin "2") (pinfunction "2_2") (pintype "passive"))
      (node (ref "J37") (pin "2") (pinfunction "2_2") (pintype "passive"))
      (node (ref "J38") (pin "2") (pinfunction "2_2") (pintype "passive"))
      (node (ref "SHFT_TO_SIGNAL_13") (pin "1") (pinfunction "1_1") (pintype "passive"))
      (node (ref "TLC_TO_SIGNAL_13") (pin "2") (pinfunction "2_2") (pintype "passive"))
    )
    (net (code "69") (name "OUT_SIGNAL_14") (class "Default")
      (node (ref "J22") (pin "3") (pinfunction "3_3") (pintype "passive"))
      (node (ref "J23") (pin "3") (pinfunction "3_3") (pintype "passive"))
      (node (ref "J37") (pin "3") (pinfunction "3_3") (pintype "passive"))
      (node (ref "J38") (pin "3") (pinfunction "3_3") (pintype "passive"))
      (node (ref "SHFT_TO_SIGNAL_14") (pin "1") (pinfunction "1_1") (pintype "passive"))
      (node (ref "TLC_TO_SIGNAL_14") (pin "2") (pinfunction "2_2") (pintype "passive"))
    )
    (net (code "70") (name "OUT_SIGNAL_15") (class "Default")
      (node (ref "J22") (pin "4") (pinfunction "4_4") (pintype "passive"))
      (node (ref "J23") (pin "4") (pinfunction "4_4") (pintype "passive"))
      (node (ref "J37") (pin "4") (pinfunction "4_4") (pintype "passive"))
      (node (ref "J38") (pin "4") (pinfunction "4_4") (pintype "passive"))
      (node (ref "SHFT_TO_SIGNAL_15") (pin "1") (pinfunction "1_1") (pintype "passive"))
      (node (ref "TLC_TO_SIGNAL_15") (pin "2") (pinfunction "2_2") (pintype "passive"))
    )
    (net (code "71") (name "OUT_SIGNAL_16") (class "Default")
      (node (ref "J22") (pin "6") (pinfunction "6_6") (pintype "passive"))
      (node (ref "J23") (pin "6") (pinfunction "6_6") (pintype "passive"))
      (node (ref "J37") (pin "6") (pinfunction "6_6") (pintype "passive"))
      (node (ref "J38") (pin "6") (pinfunction "6_6") (pintype "passive"))
      (node (ref "SHFT_TO_SIGNAL_16") (pin "1") (pinfunction "1_1") (pintype "passive"))
      (node (ref "TLC_TO_SIGNAL_16") (pin "2") (pinfunction "2_2") (pintype "passive"))
    )
    (net (code "72") (name "OUT_SIGNAL_17") (class "Default")
      (node (ref "J22") (pin "7") (pinfunction "7_7") (pintype "passive"))
      (node (ref "J23") (pin "7") (pinfunction "7_7") (pintype "passive"))
      (node (ref "J37") (pin "7") (pinfunction "7_7") (pintype "passive"))
      (node (ref "J38") (pin "7") (pinfunction "7_7") (pintype "passive"))
      (node (ref "SHFT_REG_4") (pin "15") (pinfunction "QA_15") (pintype "tri_state"))
      (node (ref "TLC_2") (pin "28") (pinfunction "OUT0_28") (pintype "output"))
    )
    (net (code "73") (name "OUT_SIGNAL_18") (class "Default")
      (node (ref "J22") (pin "8") (pinfunction "8_8") (pintype "passive"))
      (node (ref "J23") (pin "8") (pinfunction "8_8") (pintype "passive"))
      (node (ref "J37") (pin "8") (pinfunction "8_8") (pintype "passive"))
      (node (ref "J38") (pin "8") (pinfunction "8_8") (pintype "passive"))
      (node (ref "SHFT_REG_4") (pin "1") (pinfunction "QB_1") (pintype "tri_state"))
      (node (ref "TLC_2") (pin "1") (pinfunction "OUT1_1") (pintype "output"))
    )
    (net (code "74") (name "OUT_SIGNAL_19") (class "Default")
      (node (ref "J22") (pin "10") (pinfunction "10_10") (pintype "passive"))
      (node (ref "J23") (pin "10") (pinfunction "10_10") (pintype "passive"))
      (node (ref "J37") (pin "10") (pinfunction "10_10") (pintype "passive"))
      (node (ref "J38") (pin "10") (pinfunction "10_10") (pintype "passive"))
      (node (ref "SHFT_REG_4") (pin "2") (pinfunction "QC_2") (pintype "tri_state"))
      (node (ref "TLC_2") (pin "2") (pinfunction "OUT2_2") (pintype "output"))
    )
    (net (code "75") (name "OUT_SIGNAL_20") (class "Default")
      (node (ref "J22") (pin "11") (pinfunction "11_11") (pintype "passive"))
      (node (ref "J23") (pin "11") (pinfunction "11_11") (pintype "passive"))
      (node (ref "J37") (pin "11") (pinfunction "11_11") (pintype "passive"))
      (node (ref "J38") (pin "11") (pinfunction "11_11") (pintype "passive"))
      (node (ref "SHFT_REG_4") (pin "3") (pinfunction "QD_3") (pintype "tri_state"))
      (node (ref "TLC_2") (pin "3") (pinfunction "OUT3_3") (pintype "output"))
    )
    (net (code "76") (name "OUT_SIGNAL_21") (class "Default")
      (node (ref "J22") (pin "12") (pinfunction "12_12") (pintype "passive"))
      (node (ref "J23") (pin "12") (pinfunction "12_12") (pintype "passive"))
      (node (ref "J37") (pin "12") (pinfunction "12_12") (pintype "passive"))
      (node (ref "J38") (pin "12") (pinfunction "12_12") (pintype "passive"))
      (node (ref "SHFT_REG_4") (pin "4") (pinfunction "QE_4") (pintype "tri_state"))
      (node (ref "TLC_2") (pin "4") (pinfunction "OUT4_4") (pintype "output"))
    )
    (net (code "77") (name "OUT_SIGNAL_22") (class "Default")
      (node (ref "J22") (pin "14") (pinfunction "14_14") (pintype "passive"))
      (node (ref "J23") (pin "14") (pinfunction "14_14") (pintype "passive"))
      (node (ref "J37") (pin "14") (pinfunction "14_14") (pintype "passive"))
      (node (ref "J38") (pin "14") (pinfunction "14_14") (pintype "passive"))
      (node (ref "SHFT_REG_4") (pin "5") (pinfunction "QF_5") (pintype "tri_state"))
      (node (ref "TLC_2") (pin "5") (pinfunction "OUT5_5") (pintype "output"))
    )
    (net (code "78") (name "OUT_SIGNAL_23") (class "Default")
      (node (ref "J22") (pin "15") (pinfunction "15_15") (pintype "passive"))
      (node (ref "J23") (pin "15") (pinfunction "15_15") (pintype "passive"))
      (node (ref "J37") (pin "15") (pinfunction "15_15") (pintype "passive"))
      (node (ref "J38") (pin "15") (pinfunction "15_15") (pintype "passive"))
      (node (ref "SHFT_REG_4") (pin "6") (pinfunction "QG_6") (pintype "tri_state"))
      (node (ref "TLC_2") (pin "6") (pinfunction "OUT6_6") (pintype "output"))
    )
    (net (code "79") (name "OUT_SIGNAL_24") (class "Default")
      (node (ref "J22") (pin "16") (pinfunction "16_16") (pintype "passive"))
      (node (ref "J23") (pin "16") (pinfunction "16_16") (pintype "passive"))
      (node (ref "J37") (pin "16") (pinfunction "16_16") (pintype "passive"))
      (node (ref "J38") (pin "16") (pinfunction "16_16") (pintype "passive"))
      (node (ref "SHFT_REG_4") (pin "7") (pinfunction "QH_7") (pintype "tri_state"))
      (node (ref "TLC_2") (pin "7") (pinfunction "OUT7_7") (pintype "output"))
    )
    (net (code "80") (name "OUT_SIGNAL_25") (class "Default")
      (node (ref "J24") (pin "2") (pinfunction "2_2") (pintype "passive"))
      (node (ref "J25") (pin "2") (pinfunction "2_2") (pintype "passive"))
      (node (ref "SHFT_REG_3") (pin "15") (pinfunction "QA_15") (pintype "tri_state"))
      (node (ref "TLC_2") (pin "8") (pinfunction "OUT8_8") (pintype "output"))
    )
    (net (code "81") (name "OUT_SIGNAL_26") (class "Default")
      (node (ref "J24") (pin "3") (pinfunction "3_3") (pintype "passive"))
      (node (ref "J25") (pin "3") (pinfunction "3_3") (pintype "passive"))
      (node (ref "SHFT_REG_3") (pin "1") (pinfunction "QB_1") (pintype "tri_state"))
      (node (ref "TLC_2") (pin "9") (pinfunction "OUT9_9") (pintype "output"))
    )
    (net (code "82") (name "OUT_SIGNAL_27") (class "Default")
      (node (ref "J24") (pin "4") (pinfunction "4_4") (pintype "passive"))
      (node (ref "J25") (pin "4") (pinfunction "4_4") (pintype "passive"))
      (node (ref "SHFT_REG_3") (pin "2") (pinfunction "QC_2") (pintype "tri_state"))
      (node (ref "TLC_2") (pin "10") (pinfunction "OUT10_10") (pintype "output"))
    )
    (net (code "83") (name "OUT_SIGNAL_28") (class "Default")
      (node (ref "J24") (pin "6") (pinfunction "6_6") (pintype "passive"))
      (node (ref "J25") (pin "6") (pinfunction "6_6") (pintype "passive"))
      (node (ref "SHFT_REG_3") (pin "3") (pinfunction "QD_3") (pintype "tri_state"))
      (node (ref "TLC_2") (pin "11") (pinfunction "OUT11_11") (pintype "output"))
    )
    (net (code "84") (name "OUT_SIGNAL_29") (class "Default")
      (node (ref "J24") (pin "7") (pinfunction "7_7") (pintype "passive"))
      (node (ref "J25") (pin "7") (pinfunction "7_7") (pintype "passive"))
      (node (ref "SHFT_REG_3") (pin "4") (pinfunction "QE_4") (pintype "tri_state"))
      (node (ref "TLC_2") (pin "12") (pinfunction "OUT12_12") (pintype "output"))
    )
    (net (code "85") (name "OUT_SIGNAL_30") (class "Default")
      (node (ref "J24") (pin "8") (pinfunction "8_8") (pintype "passive"))
      (node (ref "J25") (pin "8") (pinfunction "8_8") (pintype "passive"))
      (node (ref "SHFT_REG_3") (pin "5") (pinfunction "QF_5") (pintype "tri_state"))
      (node (ref "TLC_2") (pin "13") (pinfunction "OUT13_13") (pintype "output"))
    )
    (net (code "86") (name "OUT_SIGNAL_31") (class "Default")
      (node (ref "J24") (pin "10") (pinfunction "10_10") (pintype "passive"))
      (node (ref "J25") (pin "10") (pinfunction "10_10") (pintype "passive"))
      (node (ref "SHFT_REG_3") (pin "6") (pinfunction "QG_6") (pintype "tri_state"))
      (node (ref "TLC_2") (pin "14") (pinfunction "OUT14_14") (pintype "output"))
    )
    (net (code "87") (name "OUT_SIGNAL_32") (class "Default")
      (node (ref "J24") (pin "11") (pinfunction "11_11") (pintype "passive"))
      (node (ref "J25") (pin "11") (pinfunction "11_11") (pintype "passive"))
      (node (ref "SHFT_REG_3") (pin "7") (pinfunction "QH_7") (pintype "tri_state"))
      (node (ref "TLC_2") (pin "15") (pinfunction "OUT15_15") (pintype "output"))
    )
    (net (code "88") (name "OUT_SIGNAL_33") (class "Default")
      (node (ref "J24") (pin "12") (pinfunction "12_12") (pintype "passive"))
      (node (ref "J25") (pin "12") (pinfunction "12_12") (pintype "passive"))
      (node (ref "SHFT_REG_5") (pin "15") (pinfunction "QA_15") (pintype "tri_state"))
      (node (ref "TLC_3") (pin "28") (pinfunction "OUT0_28") (pintype "output"))
    )
    (net (code "89") (name "OUT_SIGNAL_34") (class "Default")
      (node (ref "J24") (pin "14") (pinfunction "14_14") (pintype "passive"))
      (node (ref "J25") (pin "14") (pinfunction "14_14") (pintype "passive"))
      (node (ref "SHFT_REG_5") (pin "1") (pinfunction "QB_1") (pintype "tri_state"))
      (node (ref "TLC_3") (pin "1") (pinfunction "OUT1_1") (pintype "output"))
    )
    (net (code "90") (name "OUT_SIGNAL_35") (class "Default")
      (node (ref "J24") (pin "15") (pinfunction "15_15") (pintype "passive"))
      (node (ref "J25") (pin "15") (pinfunction "15_15") (pintype "passive"))
      (node (ref "SHFT_REG_5") (pin "2") (pinfunction "QC_2") (pintype "tri_state"))
      (node (ref "TLC_3") (pin "2") (pinfunction "OUT2_2") (pintype "output"))
    )
    (net (code "91") (name "OUT_SIGNAL_36") (class "Default")
      (node (ref "J24") (pin "16") (pinfunction "16_16") (pintype "passive"))
      (node (ref "J25") (pin "16") (pinfunction "16_16") (pintype "passive"))
      (node (ref "SHFT_REG_5") (pin "3") (pinfunction "QD_3") (pintype "tri_state"))
      (node (ref "TLC_3") (pin "3") (pinfunction "OUT3_3") (pintype "output"))
    )
    (net (code "92") (name "OUT_SIGNAL_37") (class "Default")
      (node (ref "J26") (pin "2") (pinfunction "2_2") (pintype "passive"))
      (node (ref "J27") (pin "2") (pinfunction "2_2") (pintype "passive"))
      (node (ref "SHFT_REG_5") (pin "4") (pinfunction "QE_4") (pintype "tri_state"))
      (node (ref "TLC_3") (pin "4") (pinfunction "OUT4_4") (pintype "output"))
    )
    (net (code "93") (name "OUT_SIGNAL_38") (class "Default")
      (node (ref "J26") (pin "3") (pinfunction "3_3") (pintype "passive"))
      (node (ref "J27") (pin "3") (pinfunction "3_3") (pintype "passive"))
      (node (ref "SHFT_REG_5") (pin "5") (pinfunction "QF_5") (pintype "tri_state"))
      (node (ref "TLC_3") (pin "5") (pinfunction "OUT5_5") (pintype "output"))
    )
    (net (code "94") (name "OUT_SIGNAL_39") (class "Default")
      (node (ref "J26") (pin "4") (pinfunction "4_4") (pintype "passive"))
      (node (ref "J27") (pin "4") (pinfunction "4_4") (pintype "passive"))
      (node (ref "SHFT_REG_5") (pin "6") (pinfunction "QG_6") (pintype "tri_state"))
      (node (ref "TLC_3") (pin "6") (pinfunction "OUT6_6") (pintype "output"))
    )
    (net (code "95") (name "OUT_SIGNAL_40") (class "Default")
      (node (ref "J26") (pin "6") (pinfunction "6_6") (pintype "passive"))
      (node (ref "J27") (pin "6") (pinfunction "6_6") (pintype "passive"))
      (node (ref "SHFT_REG_5") (pin "7") (pinfunction "QH_7") (pintype "tri_state"))
      (node (ref "TLC_3") (pin "7") (pinfunction "OUT7_7") (pintype "output"))
    )
    (net (code "96") (name "OUT_SIGNAL_41") (class "Default")
      (node (ref "J26") (pin "7") (pinfunction "7_7") (pintype "passive"))
      (node (ref "J27") (pin "7") (pinfunction "7_7") (pintype "passive"))
      (node (ref "TLC_3") (pin "8") (pinfunction "OUT8_8") (pintype "output"))
    )
    (net (code "97") (name "OUT_SIGNAL_42") (class "Default")
      (node (ref "J26") (pin "8") (pinfunction "8_8") (pintype "passive"))
      (node (ref "J27") (pin "8") (pinfunction "8_8") (pintype "passive"))
      (node (ref "TLC_3") (pin "9") (pinfunction "OUT9_9") (pintype "output"))
    )
    (net (code "98") (name "OUT_SIGNAL_43") (class "Default")
      (node (ref "J26") (pin "10") (pinfunction "10_10") (pintype "passive"))
      (node (ref "J27") (pin "10") (pinfunction "10_10") (pintype "passive"))
      (node (ref "TLC_3") (pin "10") (pinfunction "OUT10_10") (pintype "output"))
    )
    (net (code "99") (name "OUT_SIGNAL_44") (class "Default")
      (node (ref "J26") (pin "11") (pinfunction "11_11") (pintype "passive"))
      (node (ref "J27") (pin "11") (pinfunction "11_11") (pintype "passive"))
      (node (ref "TLC_3") (pin "11") (pinfunction "OUT11_11") (pintype "output"))
    )
    (net (code "100") (name "OUT_SIGNAL_45") (class "Default")
      (node (ref "J26") (pin "12") (pinfunction "12_12") (pintype "passive"))
      (node (ref "J27") (pin "12") (pinfunction "12_12") (pintype "passive"))
      (node (ref "TLC_3") (pin "12") (pinfunction "OUT12_12") (pintype "output"))
    )
    (net (code "101") (name "OUT_SIGNAL_46") (class "Default")
      (node (ref "J26") (pin "14") (pinfunction "14_14") (pintype "passive"))
      (node (ref "J27") (pin "14") (pinfunction "14_14") (pintype "passive"))
      (node (ref "TLC_3") (pin "13") (pinfunction "OUT13_13") (pintype "output"))
    )
    (net (code "102") (name "OUT_SIGNAL_47") (class "Default")
      (node (ref "J26") (pin "15") (pinfunction "15_15") (pintype "passive"))
      (node (ref "J27") (pin "15") (pinfunction "15_15") (pintype "passive"))
      (node (ref "TLC_3") (pin "14") (pinfunction "OUT14_14") (pintype "output"))
    )
    (net (code "103") (name "OUT_SIGNAL_48") (class "Default")
      (node (ref "J26") (pin "16") (pinfunction "16_16") (pintype "passive"))
      (node (ref "J27") (pin "16") (pinfunction "16_16") (pintype "passive"))
      (node (ref "TLC_3") (pin "15") (pinfunction "OUT15_15") (pintype "output"))
    )
    (net (code "104") (name "RX") (class "Default")
      (node (ref "B1") (pin "RX") (pinfunction "RX_RX") (pintype "bidirectional"))
      (node (ref "J1") (pin "2") (pinfunction "2_2") (pintype "passive"))
      (node (ref "J2") (pin "2") (pinfunction "2_2") (pintype "passive"))
      (node (ref "J5") (pin "1") (pinfunction "1_1") (pintype "passive"))
      (node (ref "J6") (pin "1") (pinfunction "1_1") (pintype "passive"))
      (node (ref "U$1") (pin "RX1") (pinfunction "RX1_RX1") (pintype "bidirectional"))
    )
    (net (code "105") (name "SHFT_OUT_SIGNAL_01") (class "Default")
      (node (ref "J41") (pin "1") (pinfunction "1_1") (pintype "passive"))
      (node (ref "J42") (pin "1") (pinfunction "1_1") (pintype "passive"))
      (node (ref "SHFT_REG_1") (pin "15") (pinfunction "QA_15") (pintype "tri_state"))
      (node (ref "SHFT_TO_SIGNAL_01") (pin "2") (pinfunction "2_2") (pintype "passive"))
    )
    (net (code "106") (name "SHFT_OUT_SIGNAL_02") (class "Default")
      (node (ref "J41") (pin "2") (pinfunction "2_2") (pintype "passive"))
      (node (ref "J42") (pin "2") (pinfunction "2_2") (pintype "passive"))
      (node (ref "SHFT_REG_1") (pin "1") (pinfunction "QB_1") (pintype "tri_state"))
      (node (ref "SHFT_TO_SIGNAL_02") (pin "2") (pinfunction "2_2") (pintype "passive"))
    )
    (net (code "107") (name "SHFT_OUT_SIGNAL_03") (class "Default")
      (node (ref "J41") (pin "3") (pinfunction "3_3") (pintype "passive"))
      (node (ref "J42") (pin "3") (pinfunction "3_3") (pintype "passive"))
      (node (ref "SHFT_REG_1") (pin "2") (pinfunction "QC_2") (pintype "tri_state"))
      (node (ref "SHFT_TO_SIGNAL_03") (pin "2") (pinfunction "2_2") (pintype "passive"))
    )
    (net (code "108") (name "SHFT_OUT_SIGNAL_04") (class "Default")
      (node (ref "J41") (pin "4") (pinfunction "4_4") (pintype "passive"))
      (node (ref "J42") (pin "4") (pinfunction "4_4") (pintype "passive"))
      (node (ref "SHFT_REG_1") (pin "3") (pinfunction "QD_3") (pintype "tri_state"))
      (node (ref "SHFT_TO_SIGNAL_04") (pin "2") (pinfunction "2_2") (pintype "passive"))
    )
    (net (code "109") (name "SHFT_OUT_SIGNAL_05") (class "Default")
      (node (ref "J41") (pin "5") (pinfunction "5_5") (pintype "passive"))
      (node (ref "J42") (pin "5") (pinfunction "5_5") (pintype "passive"))
      (node (ref "SHFT_REG_1") (pin "4") (pinfunction "QE_4") (pintype "tri_state"))
      (node (ref "SHFT_TO_SIGNAL_05") (pin "2") (pinfunction "2_2") (pintype "passive"))
    )
    (net (code "110") (name "SHFT_OUT_SIGNAL_06") (class "Default")
      (node (ref "J41") (pin "6") (pinfunction "6_6") (pintype "passive"))
      (node (ref "J42") (pin "6") (pinfunction "6_6") (pintype "passive"))
      (node (ref "SHFT_REG_1") (pin "5") (pinfunction "QF_5") (pintype "tri_state"))
      (node (ref "SHFT_TO_SIGNAL_06") (pin "2") (pinfunction "2_2") (pintype "passive"))
    )
    (net (code "111") (name "SHFT_OUT_SIGNAL_07") (class "Default")
      (node (ref "J41") (pin "7") (pinfunction "7_7") (pintype "passive"))
      (node (ref "J42") (pin "7") (pinfunction "7_7") (pintype "passive"))
      (node (ref "SHFT_REG_1") (pin "6") (pinfunction "QG_6") (pintype "tri_state"))
      (node (ref "SHFT_TO_SIGNAL_07") (pin "2") (pinfunction "2_2") (pintype "passive"))
    )
    (net (code "112") (name "SHFT_OUT_SIGNAL_08") (class "Default")
      (node (ref "J41") (pin "8") (pinfunction "8_8") (pintype "passive"))
      (node (ref "J42") (pin "8") (pinfunction "8_8") (pintype "passive"))
      (node (ref "SHFT_REG_1") (pin "7") (pinfunction "QH_7") (pintype "tri_state"))
      (node (ref "SHFT_TO_SIGNAL_08") (pin "2") (pinfunction "2_2") (pintype "passive"))
    )
    (net (code "113") (name "SHFT_OUT_SIGNAL_09") (class "Default")
      (node (ref "J41") (pin "9") (pinfunction "9_9") (pintype "passive"))
      (node (ref "J42") (pin "9") (pinfunction "9_9") (pintype "passive"))
      (node (ref "SHFT_REG_2") (pin "15") (pinfunction "QA_15") (pintype "tri_state"))
      (node (ref "SHFT_TO_SIGNAL_09") (pin "2") (pinfunction "2_2") (pintype "passive"))
    )
    (net (code "114") (name "SHFT_OUT_SIGNAL_10") (class "Default")
      (node (ref "J41") (pin "10") (pinfunction "10_10") (pintype "passive"))
      (node (ref "J42") (pin "10") (pinfunction "10_10") (pintype "passive"))
      (node (ref "SHFT_REG_2") (pin "1") (pinfunction "QB_1") (pintype "tri_state"))
      (node (ref "SHFT_TO_SIGNAL_10") (pin "2") (pinfunction "2_2") (pintype "passive"))
    )
    (net (code "115") (name "SHFT_OUT_SIGNAL_11") (class "Default")
      (node (ref "J41") (pin "11") (pinfunction "11_11") (pintype "passive"))
      (node (ref "J42") (pin "11") (pinfunction "11_11") (pintype "passive"))
      (node (ref "SHFT_REG_2") (pin "2") (pinfunction "QC_2") (pintype "tri_state"))
      (node (ref "SHFT_TO_SIGNAL_11") (pin "2") (pinfunction "2_2") (pintype "passive"))
    )
    (net (code "116") (name "SHFT_OUT_SIGNAL_12") (class "Default")
      (node (ref "J41") (pin "12") (pinfunction "12_12") (pintype "passive"))
      (node (ref "J42") (pin "12") (pinfunction "12_12") (pintype "passive"))
      (node (ref "SHFT_REG_2") (pin "3") (pinfunction "QD_3") (pintype "tri_state"))
      (node (ref "SHFT_TO_SIGNAL_12") (pin "2") (pinfunction "2_2") (pintype "passive"))
    )
    (net (code "117") (name "SHFT_OUT_SIGNAL_13") (class "Default")
      (node (ref "J41") (pin "13") (pinfunction "13_13") (pintype "passive"))
      (node (ref "J42") (pin "13") (pinfunction "13_13") (pintype "passive"))
      (node (ref "SHFT_REG_2") (pin "4") (pinfunction "QE_4") (pintype "tri_state"))
      (node (ref "SHFT_TO_SIGNAL_13") (pin "2") (pinfunction "2_2") (pintype "passive"))
    )
    (net (code "118") (name "SHFT_OUT_SIGNAL_14") (class "Default")
      (node (ref "J41") (pin "14") (pinfunction "14_14") (pintype "passive"))
      (node (ref "J42") (pin "14") (pinfunction "14_14") (pintype "passive"))
      (node (ref "SHFT_REG_2") (pin "5") (pinfunction "QF_5") (pintype "tri_state"))
      (node (ref "SHFT_TO_SIGNAL_14") (pin "2") (pinfunction "2_2") (pintype "passive"))
    )
    (net (code "119") (name "SHFT_OUT_SIGNAL_15") (class "Default")
      (node (ref "J41") (pin "15") (pinfunction "15_15") (pintype "passive"))
      (node (ref "J42") (pin "15") (pinfunction "15_15") (pintype "passive"))
      (node (ref "SHFT_REG_2") (pin "6") (pinfunction "QG_6") (pintype "tri_state"))
      (node (ref "SHFT_TO_SIGNAL_15") (pin "2") (pinfunction "2_2") (pintype "passive"))
    )
    (net (code "120") (name "SHFT_OUT_SIGNAL_16") (class "Default")
      (node (ref "J41") (pin "16") (pinfunction "16_16") (pintype "passive"))
      (node (ref "J42") (pin "16") (pinfunction "16_16") (pintype "passive"))
      (node (ref "SHFT_REG_2") (pin "7") (pinfunction "QH_7") (pintype "tri_state"))
      (node (ref "SHFT_TO_SIGNAL_16") (pin "2") (pinfunction "2_2") (pintype "passive"))
    )
    (net (code "121") (name "SHFT_REG_1_OUT") (class "Default")
      (node (ref "SHFT_REG_1") (pin "9") (pinfunction "QH*_9") (pintype "tri_state"))
      (node (ref "SHFT_REG_2") (pin "14") (pinfunction "SER_14") (pintype "input"))
    )
    (net (code "122") (name "SHFT_REG_2_OUT") (class "Default")
      (node (ref "SHFT_REG_2") (pin "9") (pinfunction "QH*_9") (pintype "tri_state"))
      (node (ref "SHFT_REG_4") (pin "14") (pinfunction "SER_14") (pintype "input"))
    )
    (net (code "123") (name "SHFT_REG_3_SOUT") (class "Default")
      (node (ref "SHFT_REG_3") (pin "14") (pinfunction "SER_14") (pintype "input"))
      (node (ref "SHFT_REG_4") (pin "9") (pinfunction "QH*_9") (pintype "tri_state"))
    )
    (net (code "124") (name "SHFT_REG_4_SOUT") (class "Default")
      (node (ref "SHFT_REG_3") (pin "9") (pinfunction "QH*_9") (pintype "tri_state"))
      (node (ref "SHFT_REG_5") (pin "14") (pinfunction "SER_14") (pintype "input"))
    )
    (net (code "125") (name "SHFT_REG_OE") (class "Default")
      (node (ref "D6_TO_SHFT_OE") (pin "2") (pinfunction "2_2") (pintype "passive"))
      (node (ref "GEN_4_TO_SHFT_OE") (pin "2") (pinfunction "2_2") (pintype "passive"))
      (node (ref "GND_TO_SHFT_OE") (pin "2") (pinfunction "2_2") (pintype "passive"))
      (node (ref "SHFT_REG_1") (pin "13") (pinfunction "G_13") (pintype "input"))
      (node (ref "SHFT_REG_2") (pin "13") (pinfunction "G_13") (pintype "input"))
      (node (ref "SHFT_REG_3") (pin "13") (pinfunction "G_13") (pintype "input"))
      (node (ref "SHFT_REG_4") (pin "13") (pinfunction "G_13") (pintype "input"))
      (node (ref "SHFT_REG_5") (pin "13") (pinfunction "G_13") (pintype "input"))
    )
    (net (code "126") (name "SHFT_REG_RCK") (class "Default")
      (node (ref "D4_TO_SHFT_RCK") (pin "2") (pinfunction "2_2") (pintype "passive"))
      (node (ref "GEN_2_TO_SHFT_RCK") (pin "2") (pinfunction "2_2") (pintype "passive"))
      (node (ref "SHFT_REG_1") (pin "12") (pinfunction "RCK_12") (pintype "input"))
      (node (ref "SHFT_REG_3") (pin "12") (pinfunction "RCK_12") (pintype "input"))
      (node (ref "SHFT_REG_4") (pin "12") (pinfunction "RCK_12") (pintype "input"))
      (node (ref "SHFT_REG_5") (pin "12") (pinfunction "RCK_12") (pintype "input"))
    )
    (net (code "127") (name "SHFT_REG_SCK") (class "Default")
      (node (ref "D3_TO_SHFT_SCK") (pin "2") (pinfunction "2_2") (pintype "passive"))
      (node (ref "GEN_1_TO_SHFT_SCK") (pin "2") (pinfunction "2_2") (pintype "passive"))
      (node (ref "SHFT_REG_1") (pin "11") (pinfunction "SCK_11") (pintype "input"))
      (node (ref "SHFT_REG_2") (pin "11") (pinfunction "SCK_11") (pintype "input"))
      (node (ref "SHFT_REG_3") (pin "11") (pinfunction "SCK_11") (pintype "input"))
      (node (ref "SHFT_REG_4") (pin "11") (pinfunction "SCK_11") (pintype "input"))
      (node (ref "SHFT_REG_5") (pin "11") (pinfunction "SCK_11") (pintype "input"))
    )
    (net (code "128") (name "SHFT_REG_SCL") (class "Default")
      (node (ref "D5_TO_SHFT_SCL") (pin "2") (pinfunction "2_2") (pintype "passive"))
      (node (ref "GEN_3_TO_SHFT_SCL") (pin "2") (pinfunction "2_2") (pintype "passive"))
      (node (ref "SHFT_REG_1") (pin "10") (pinfunction "SCL_10") (pintype "input"))
      (node (ref "SHFT_REG_2") (pin "10") (pinfunction "SCL_10") (pintype "input"))
      (node (ref "SHFT_REG_3") (pin "10") (pinfunction "SCL_10") (pintype "input"))
      (node (ref "SHFT_REG_4") (pin "10") (pinfunction "SCL_10") (pintype "input"))
      (node (ref "SHFT_REG_5") (pin "10") (pinfunction "SCL_10") (pintype "input"))
    )
    (net (code "129") (name "SHFT_REG_SERIAL_IN") (class "Default")
      (node (ref "D2_TO_SHFT_SER_IN") (pin "2") (pinfunction "2_2") (pintype "passive"))
      (node (ref "GEN_0_TO_SHFT_SER_IN") (pin "2") (pinfunction "2_2") (pintype "passive"))
      (node (ref "SHFT_REG_1") (pin "14") (pinfunction "SER_14") (pintype "input"))
    )
    (net (code "130") (name "SHIFT_REG_RCK") (class "Default")
      (node (ref "SHFT_REG_2") (pin "12") (pinfunction "RCK_12") (pintype "input"))
    )
    (net (code "131") (name "TINY03") (class "Default")
      (node (ref "J14") (pin "2") (pinfunction "2_2") (pintype "passive"))
      (node (ref "J15") (pin "2") (pinfunction "2_2") (pintype "passive"))
      (node (ref "J16") (pin "2") (pinfunction "2_2") (pintype "passive"))
      (node (ref "TINY3_GEN_3") (pin "1") (pinfunction "1_1") (pintype "passive"))
      (node (ref "U1") (pin "2") (pinfunction "PB3_2") (pintype "bidirectional"))
    )
    (net (code "132") (name "TINY04") (class "Default")
      (node (ref "J14") (pin "3") (pinfunction "3_3") (pintype "passive"))
      (node (ref "J15") (pin "3") (pinfunction "3_3") (pintype "passive"))
      (node (ref "J16") (pin "3") (pinfunction "3_3") (pintype "passive"))
      (node (ref "U1") (pin "3") (pinfunction "PB4_3") (pintype "bidirectional"))
    )
    (net (code "133") (name "TINYRST") (class "Default")
      (node (ref "ARDUINO_ISP") (pin "2") (pinfunction "2_2") (pintype "passive"))
      (node (ref "ICP_FOR_SMALL") (pin "1") (pinfunction "1_1") (pintype "passive"))
      (node (ref "J14") (pin "1") (pinfunction "1_1") (pintype "passive"))
      (node (ref "J15") (pin "1") (pinfunction "1_1") (pintype "passive"))
      (node (ref "J16") (pin "1") (pinfunction "1_1") (pintype "passive"))
      (node (ref "U1") (pin "1") (pinfunction "NRES/PB5_1") (pintype "bidirectional"))
    )
    (net (code "134") (name "TINY_04") (class "Default")
      (node (ref "TINY4_GEN4") (pin "1") (pinfunction "1_1") (pintype "passive"))
    )
    (net (code "135") (name "TLC_BLANK") (class "Default")
      (node (ref "GEN_3_TO_TLC_BLANK") (pin "2") (pinfunction "2_2") (pintype "passive"))
      (node (ref "TLC_1") (pin "23") (pinfunction "BLANK_23") (pintype "input"))
      (node (ref "TLC_2") (pin "23") (pinfunction "BLANK_23") (pintype "input"))
      (node (ref "TLC_3") (pin "23") (pinfunction "BLANK_23") (pintype "input"))
    )
    (net (code "136") (name "TLC_DCPRG") (class "Default")
      (node (ref "PLS_SOLDER_TLC_DCPRG_CONNECT_TO_5V") (pin "1") (pinfunction "1_1") (pintype "passive"))
      (node (ref "TLC_1") (pin "19") (pinfunction "DCPRG_19") (pintype "input"))
      (node (ref "TLC_2") (pin "19") (pinfunction "DCPRG_19") (pintype "input"))
      (node (ref "TLC_3") (pin "19") (pinfunction "DCPRG_19") (pintype "input"))
    )
    (net (code "137") (name "TLC_GSCLK") (class "Default")
      (node (ref "D3_TO_TLC_GSCLK") (pin "2") (pinfunction "2_2") (pintype "passive"))
      (node (ref "GEN_1_TO_TLC_GSCLK") (pin "2") (pinfunction "2_2") (pintype "passive"))
      (node (ref "TLC_1") (pin "18") (pinfunction "GSCLK_18") (pintype "input"))
      (node (ref "TLC_2") (pin "18") (pinfunction "GSCLK_18") (pintype "input"))
      (node (ref "TLC_3") (pin "18") (pinfunction "GSCLK_18") (pintype "input"))
    )
    (net (code "138") (name "TLC_IREF_1") (class "Default")
      (node (ref "TLC_1") (pin "20") (pinfunction "IREF_20") (pintype "passive"))
      (node (ref "TLC_IREF_1_TO_GND") (pin "2") (pinfunction "2_2") (pintype "passive"))
      (node (ref "TLC_IREF_1_TO_RESISTOR") (pin "1") (pinfunction "1_1") (pintype "passive"))
    )
    (net (code "139") (name "TLC_IREF_1_RESISTOR") (class "Default")
      (node (ref "TLC_IREF_1_RES") (pin "1") (pinfunction "1_1") (pintype "passive"))
      (node (ref "TLC_IREF_1_TO_RESISTOR") (pin "2") (pinfunction "2_2") (pintype "passive"))
    )
    (net (code "140") (name "TLC_IREF_2") (class "Default")
      (node (ref "TLC_2") (pin "20") (pinfunction "IREF_20") (pintype "passive"))
      (node (ref "TLC_IREF_2_TO_GND") (pin "2") (pinfunction "2_2") (pintype "passive"))
      (node (ref "TLC_IREF_2_TO_RESISTOR") (pin "1") (pinfunction "1_1") (pintype "passive"))
    )
    (net (code "141") (name "TLC_IREF_2_RESISTOR") (class "Default")
      (node (ref "TLC_IREF_2_RES") (pin "1") (pinfunction "1_1") (pintype "passive"))
      (node (ref "TLC_IREF_2_TO_RESISTOR") (pin "2") (pinfunction "2_2") (pintype "passive"))
    )
    (net (code "142") (name "TLC_IREF_3") (class "Default")
      (node (ref "TLC_3") (pin "20") (pinfunction "IREF_20") (pintype "passive"))
      (node (ref "TLC_IREF_3_TO_GND") (pin "2") (pinfunction "2_2") (pintype "passive"))
      (node (ref "TLC_IREF_3_TO_RESISTOR") (pin "1") (pinfunction "1_1") (pintype "passive"))
    )
    (net (code "143") (name "TLC_IREF_3_RESISTOR") (class "Default")
      (node (ref "TLC_IREF_3_RES") (pin "1") (pinfunction "1_1") (pintype "passive"))
      (node (ref "TLC_IREF_3_TO_RESISTOR") (pin "2") (pinfunction "2_2") (pintype "passive"))
    )
    (net (code "144") (name "TLC_OUT_SIGNAL_01") (class "Default")
      (node (ref "J39") (pin "1") (pinfunction "1_1") (pintype "passive"))
      (node (ref "J40") (pin "1") (pinfunction "1_1") (pintype "passive"))
      (node (ref "TLC_1") (pin "28") (pinfunction "OUT0_28") (pintype "output"))
      (node (ref "TLC_TO_SIGNAL_01") (pin "1") (pinfunction "1_1") (pintype "passive"))
    )
    (net (code "145") (name "TLC_OUT_SIGNAL_02") (class "Default")
      (node (ref "J39") (pin "2") (pinfunction "2_2") (pintype "passive"))
      (node (ref "J40") (pin "2") (pinfunction "2_2") (pintype "passive"))
      (node (ref "TLC_1") (pin "1") (pinfunction "OUT1_1") (pintype "output"))
      (node (ref "TLC_TO_SIGNAL_02") (pin "1") (pinfunction "1_1") (pintype "passive"))
    )
    (net (code "146") (name "TLC_OUT_SIGNAL_03") (class "Default")
      (node (ref "J39") (pin "3") (pinfunction "3_3") (pintype "passive"))
      (node (ref "J40") (pin "3") (pinfunction "3_3") (pintype "passive"))
      (node (ref "TLC_1") (pin "2") (pinfunction "OUT2_2") (pintype "output"))
      (node (ref "TLC_TO_SIGNAL_03") (pin "1") (pinfunction "1_1") (pintype "passive"))
    )
    (net (code "147") (name "TLC_OUT_SIGNAL_04") (class "Default")
      (node (ref "J39") (pin "4") (pinfunction "4_4") (pintype "passive"))
      (node (ref "J40") (pin "4") (pinfunction "4_4") (pintype "passive"))
      (node (ref "TLC_1") (pin "3") (pinfunction "OUT3_3") (pintype "output"))
      (node (ref "TLC_TO_SIGNAL_04") (pin "1") (pinfunction "1_1") (pintype "passive"))
    )
    (net (code "148") (name "TLC_OUT_SIGNAL_05") (class "Default")
      (node (ref "J39") (pin "5") (pinfunction "5_5") (pintype "passive"))
      (node (ref "J40") (pin "5") (pinfunction "5_5") (pintype "passive"))
      (node (ref "TLC_1") (pin "4") (pinfunction "OUT4_4") (pintype "output"))
      (node (ref "TLC_TO_SIGNAL_05") (pin "1") (pinfunction "1_1") (pintype "passive"))
    )
    (net (code "149") (name "TLC_OUT_SIGNAL_06") (class "Default")
      (node (ref "J39") (pin "6") (pinfunction "6_6") (pintype "passive"))
      (node (ref "J40") (pin "6") (pinfunction "6_6") (pintype "passive"))
      (node (ref "TLC_1") (pin "5") (pinfunction "OUT5_5") (pintype "output"))
      (node (ref "TLC_TO_SIGNAL_06") (pin "1") (pinfunction "1_1") (pintype "passive"))
    )
    (net (code "150") (name "TLC_OUT_SIGNAL_07") (class "Default")
      (node (ref "J39") (pin "7") (pinfunction "7_7") (pintype "passive"))
      (node (ref "J40") (pin "7") (pinfunction "7_7") (pintype "passive"))
      (node (ref "TLC_1") (pin "6") (pinfunction "OUT6_6") (pintype "output"))
      (node (ref "TLC_TO_SIGNAL_07") (pin "1") (pinfunction "1_1") (pintype "passive"))
    )
    (net (code "151") (name "TLC_OUT_SIGNAL_08") (class "Default")
      (node (ref "J39") (pin "8") (pinfunction "8_8") (pintype "passive"))
      (node (ref "J40") (pin "8") (pinfunction "8_8") (pintype "passive"))
      (node (ref "TLC_1") (pin "7") (pinfunction "OUT7_7") (pintype "output"))
      (node (ref "TLC_TO_SIGNAL_08") (pin "1") (pinfunction "1_1") (pintype "passive"))
    )
    (net (code "152") (name "TLC_OUT_SIGNAL_09") (class "Default")
      (node (ref "J39") (pin "9") (pinfunction "9_9") (pintype "passive"))
      (node (ref "J40") (pin "9") (pinfunction "9_9") (pintype "passive"))
      (node (ref "TLC_1") (pin "8") (pinfunction "OUT8_8") (pintype "output"))
      (node (ref "TLC_TO_SIGNAL_09") (pin "1") (pinfunction "1_1") (pintype "passive"))
    )
    (net (code "153") (name "TLC_OUT_SIGNAL_10") (class "Default")
      (node (ref "J39") (pin "10") (pinfunction "10_10") (pintype "passive"))
      (node (ref "J40") (pin "10") (pinfunction "10_10") (pintype "passive"))
      (node (ref "TLC_1") (pin "9") (pinfunction "OUT9_9") (pintype "output"))
      (node (ref "TLC_TO_SIGNAL_10") (pin "1") (pinfunction "1_1") (pintype "passive"))
    )
    (net (code "154") (name "TLC_OUT_SIGNAL_11") (class "Default")
      (node (ref "J39") (pin "11") (pinfunction "11_11") (pintype "passive"))
      (node (ref "J40") (pin "11") (pinfunction "11_11") (pintype "passive"))
      (node (ref "TLC_1") (pin "10") (pinfunction "OUT10_10") (pintype "output"))
      (node (ref "TLC_TO_SIGNAL_11") (pin "1") (pinfunction "1_1") (pintype "passive"))
    )
    (net (code "155") (name "TLC_OUT_SIGNAL_12") (class "Default")
      (node (ref "J39") (pin "12") (pinfunction "12_12") (pintype "passive"))
      (node (ref "J40") (pin "12") (pinfunction "12_12") (pintype "passive"))
      (node (ref "TLC_1") (pin "11") (pinfunction "OUT11_11") (pintype "output"))
      (node (ref "TLC_TO_SIGNAL_12") (pin "1") (pinfunction "1_1") (pintype "passive"))
    )
    (net (code "156") (name "TLC_OUT_SIGNAL_13") (class "Default")
      (node (ref "J39") (pin "13") (pinfunction "13_13") (pintype "passive"))
      (node (ref "J40") (pin "13") (pinfunction "13_13") (pintype "passive"))
      (node (ref "TLC_1") (pin "12") (pinfunction "OUT12_12") (pintype "output"))
      (node (ref "TLC_TO_SIGNAL_13") (pin "1") (pinfunction "1_1") (pintype "passive"))
    )
    (net (code "157") (name "TLC_OUT_SIGNAL_14") (class "Default")
      (node (ref "J39") (pin "14") (pinfunction "14_14") (pintype "passive"))
      (node (ref "J40") (pin "14") (pinfunction "14_14") (pintype "passive"))
      (node (ref "TLC_1") (pin "13") (pinfunction "OUT13_13") (pintype "output"))
      (node (ref "TLC_TO_SIGNAL_14") (pin "1") (pinfunction "1_1") (pintype "passive"))
    )
    (net (code "158") (name "TLC_OUT_SIGNAL_15") (class "Default")
      (node (ref "J39") (pin "15") (pinfunction "15_15") (pintype "passive"))
      (node (ref "J40") (pin "15") (pinfunction "15_15") (pintype "passive"))
      (node (ref "TLC_1") (pin "14") (pinfunction "OUT14_14") (pintype "output"))
      (node (ref "TLC_TO_SIGNAL_15") (pin "1") (pinfunction "1_1") (pintype "passive"))
    )
    (net (code "159") (name "TLC_OUT_SIGNAL_16") (class "Default")
      (node (ref "J39") (pin "16") (pinfunction "16_16") (pintype "passive"))
      (node (ref "J40") (pin "16") (pinfunction "16_16") (pintype "passive"))
      (node (ref "TLC_1") (pin "15") (pinfunction "OUT15_15") (pintype "output"))
      (node (ref "TLC_TO_SIGNAL_16") (pin "1") (pinfunction "1_1") (pintype "passive"))
    )
    (net (code "160") (name "TLC_SCLK") (class "Default")
      (node (ref "GEN_2_TO_TLC_SCLK") (pin "2") (pinfunction "2_2") (pintype "passive"))
      (node (ref "TLC_1") (pin "25") (pinfunction "SCLK_25") (pintype "input"))
      (node (ref "TLC_2") (pin "25") (pinfunction "SCLK_25") (pintype "input"))
      (node (ref "TLC_3") (pin "25") (pinfunction "SCLK_25") (pintype "input"))
    )
    (net (code "161") (name "TLC_SIN_1") (class "Default")
      (node (ref "GEN_0_TO_TLC_SIN") (pin "2") (pinfunction "2_2") (pintype "passive"))
      (node (ref "TLC_1") (pin "26") (pinfunction "SIN_26") (pintype "input"))
    )
    (net (code "162") (name "TLC_SIN_2") (class "Default")
      (node (ref "TLC_2") (pin "26") (pinfunction "SIN_26") (pintype "input"))
      (node (ref "TLC_CHAIN_1_2") (pin "2") (pinfunction "2_2") (pintype "passive"))
    )
    (net (code "163") (name "TLC_SIN_3") (class "Default")
      (node (ref "TLC_3") (pin "26") (pinfunction "SIN_26") (pintype "input"))
      (node (ref "TLC_CHAIN_1_1") (pin "2") (pinfunction "2_2") (pintype "passive"))
    )
    (net (code "164") (name "TLC_SOUT_1") (class "Default")
      (node (ref "TLC_1") (pin "17") (pinfunction "SOUT_17") (pintype "output"))
      (node (ref "TLC_CHAIN_1_2") (pin "1") (pinfunction "1_1") (pintype "passive"))
    )
    (net (code "165") (name "TLC_SOUT_2") (class "Default")
      (node (ref "TLC_2") (pin "17") (pinfunction "SOUT_17") (pintype "output"))
      (node (ref "TLC_CHAIN_1_1") (pin "1") (pinfunction "1_1") (pintype "passive"))
    )
    (net (code "166") (name "TLC_SOUT_3") (class "Default")
      (node (ref "TLC_3") (pin "17") (pinfunction "SOUT_17") (pintype "output"))
    )
    (net (code "167") (name "TLC_VPRG") (class "Default")
      (node (ref "PLS_SOLDER_TLC_VPRG_CONNECT_TO_GROUD") (pin "1") (pinfunction "1_1") (pintype "passive"))
      (node (ref "TLC_1") (pin "27") (pinfunction "VPRG_27") (pintype "input"))
      (node (ref "TLC_2") (pin "27") (pinfunction "VPRG_27") (pintype "input"))
      (node (ref "TLC_3") (pin "27") (pinfunction "VPRG_27") (pintype "input"))
    )
    (net (code "168") (name "TLC_XERR") (class "Default")
      (node (ref "TLC_1") (pin "16") (pinfunction "XERR_16") (pintype "output"))
      (node (ref "TLC_2") (pin "16") (pinfunction "XERR_16") (pintype "output"))
      (node (ref "TLC_3") (pin "16") (pinfunction "XERR_16") (pintype "output"))
    )
    (net (code "169") (name "TLC_XLAT") (class "Default")
      (node (ref "GEN_3_TO_TLC_XLAT") (pin "2") (pinfunction "2_2") (pintype "passive"))
      (node (ref "TLC_1") (pin "24") (pinfunction "XLAT_24") (pintype "input"))
      (node (ref "TLC_2") (pin "24") (pinfunction "XLAT_24") (pintype "input"))
      (node (ref "TLC_3") (pin "24") (pinfunction "XLAT_24") (pintype "input"))
    )
    (net (code "170") (name "TX") (class "Default")
      (node (ref "B1") (pin "TX") (pinfunction "TX_TX") (pintype "bidirectional"))
      (node (ref "J1") (pin "1") (pinfunction "1_1") (pintype "passive"))
      (node (ref "J2") (pin "1") (pinfunction "1_1") (pintype "passive"))
      (node (ref "J5") (pin "2") (pinfunction "2_2") (pintype "passive"))
      (node (ref "J6") (pin "2") (pinfunction "2_2") (pintype "passive"))
      (node (ref "U$1") (pin "TX0") (pinfunction "TX0_TX0") (pintype "bidirectional"))
    )
    (net (code "171") (name "VCC") (class "Default")
      (node (ref "PLS_SOLDER_5V_TO_SHIFT_REGISTERS") (pin "1") (pinfunction "1_1") (pintype "passive"))
    )
    (net (code "172") (name "VIN") (class "Default")
      (node (ref "B1") (pin "VIN") (pinfunction "VIN_VIN") (pintype "bidirectional"))
      (node (ref "J10") (pin "1") (pinfunction "1_1") (pintype "passive"))
      (node (ref "J3") (pin "15") (pinfunction "15_15") (pintype "passive"))
      (node (ref "J4") (pin "15") (pinfunction "15_15") (pintype "passive"))
      (node (ref "J9") (pin "1") (pinfunction "1_1") (pintype "passive"))
      (node (ref "OUT_PWR_TO_VIN") (pin "1") (pinfunction "1_1") (pintype "passive"))
      (node (ref "U$1") (pin "RAW") (pinfunction "RAW_RAW") (pintype "bidirectional"))
    )
    (net (code "173") (name "unconnected-(B1-PadSCL)") (class "Default")
      (node (ref "B1") (pin "SCL") (pinfunction "SCL_SCL") (pintype "bidirectional"))
    )
    (net (code "174") (name "unconnected-(B1-PadSDA)") (class "Default")
      (node (ref "B1") (pin "SDA") (pinfunction "SDA_SDA") (pintype "bidirectional"))
    )
    (net (code "175") (name "unconnected-(SHFT_REG_5A-QH*-Pad9)") (class "Default")
      (node (ref "SHFT_REG_5") (pin "9") (pinfunction "QH*_9") (pintype "tri_state"))
    )
    (net (code "176") (name "unconnected-(U$1-PadA6)") (class "Default")
      (node (ref "U$1") (pin "A6") (pinfunction "A6_A6") (pintype "bidirectional"))
    )
    (net (code "177") (name "unconnected-(U$1-PadA7)") (class "Default")
      (node (ref "U$1") (pin "A7") (pinfunction "A7_A7") (pintype "bidirectional"))
    )
    (net (code "178") (name "unconnected-(U$1-PadICSP1)") (class "Default")
      (node (ref "U$1") (pin "ICSP1") (pinfunction "ICSP1_ICSP1") (pintype "bidirectional"))
    )
    (net (code "179") (name "unconnected-(U$1-PadICSP2)") (class "Default")
      (node (ref "U$1") (pin "ICSP2") (pinfunction "ICSP2_ICSP2") (pintype "bidirectional"))
    )
    (net (code "180") (name "unconnected-(U$1-PadICSP3)") (class "Default")
      (node (ref "U$1") (pin "ICSP3") (pinfunction "ICSP3_ICSP3") (pintype "bidirectional"))
    )
    (net (code "181") (name "unconnected-(U$1-PadICSP4)") (class "Default")
      (node (ref "U$1") (pin "ICSP4") (pinfunction "ICSP4_ICSP4") (pintype "bidirectional"))
    )
    (net (code "182") (name "unconnected-(U$1-PadICSP5)") (class "Default")
      (node (ref "U$1") (pin "ICSP5") (pinfunction "ICSP5_ICSP5") (pintype "bidirectional"))
    )
    (net (code "183") (name "unconnected-(U$1-PadICSP6)") (class "Default")
      (node (ref "U$1") (pin "ICSP6") (pinfunction "ICSP6_ICSP6") (pintype "bidirectional"))
    )
    (net (code "184") (name "unconnected-(U$1-PadRST1)") (class "Default")
      (node (ref "U$1") (pin "RST1") (pinfunction "RST1_RST1") (pintype "bidirectional"))
    )
  )
)
